# transponder-6_1_0.net
KiCad netlist of a schematic drawn in EAGLE
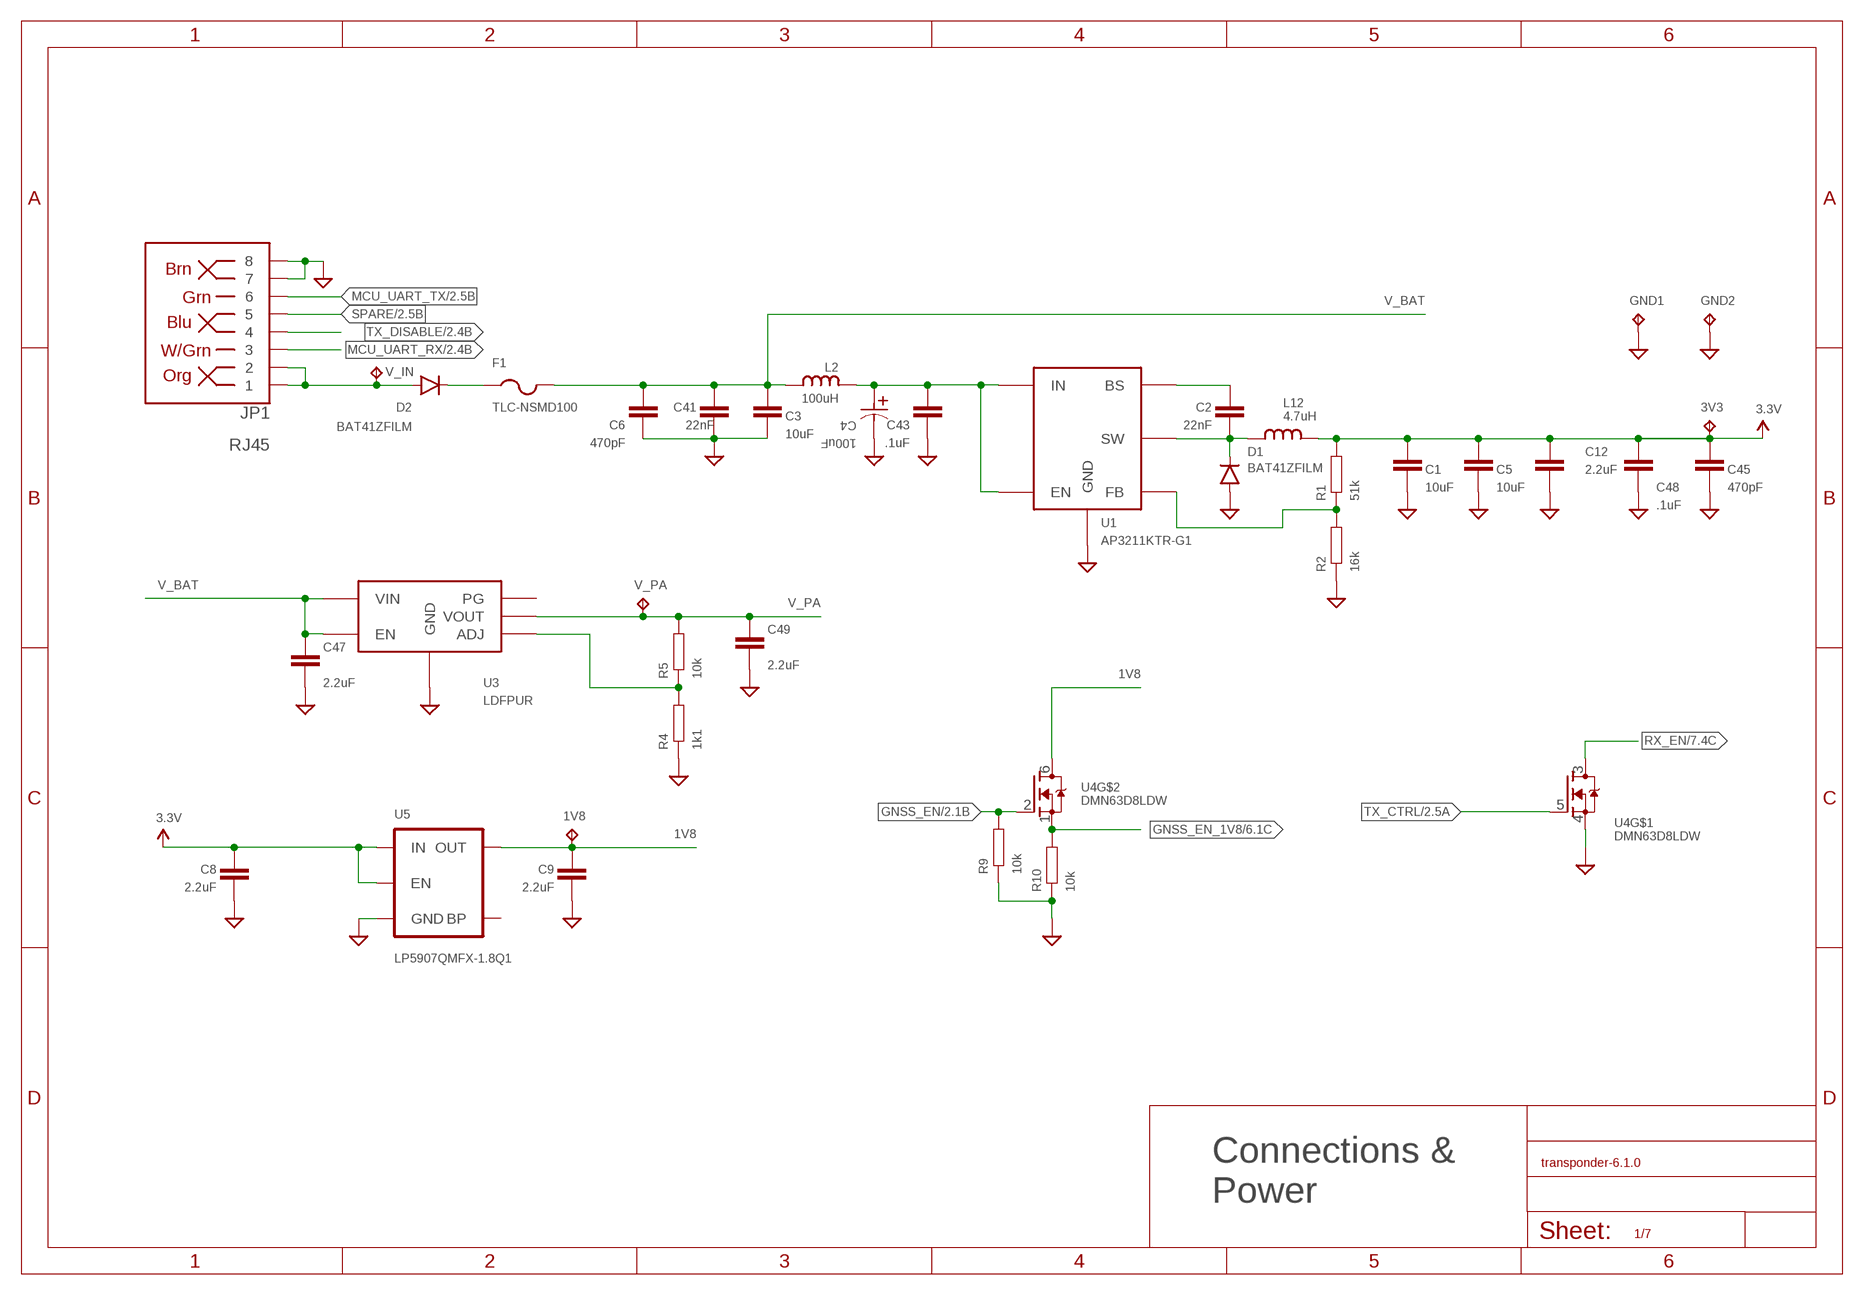
[diagram p0: schematic, sheet 1]
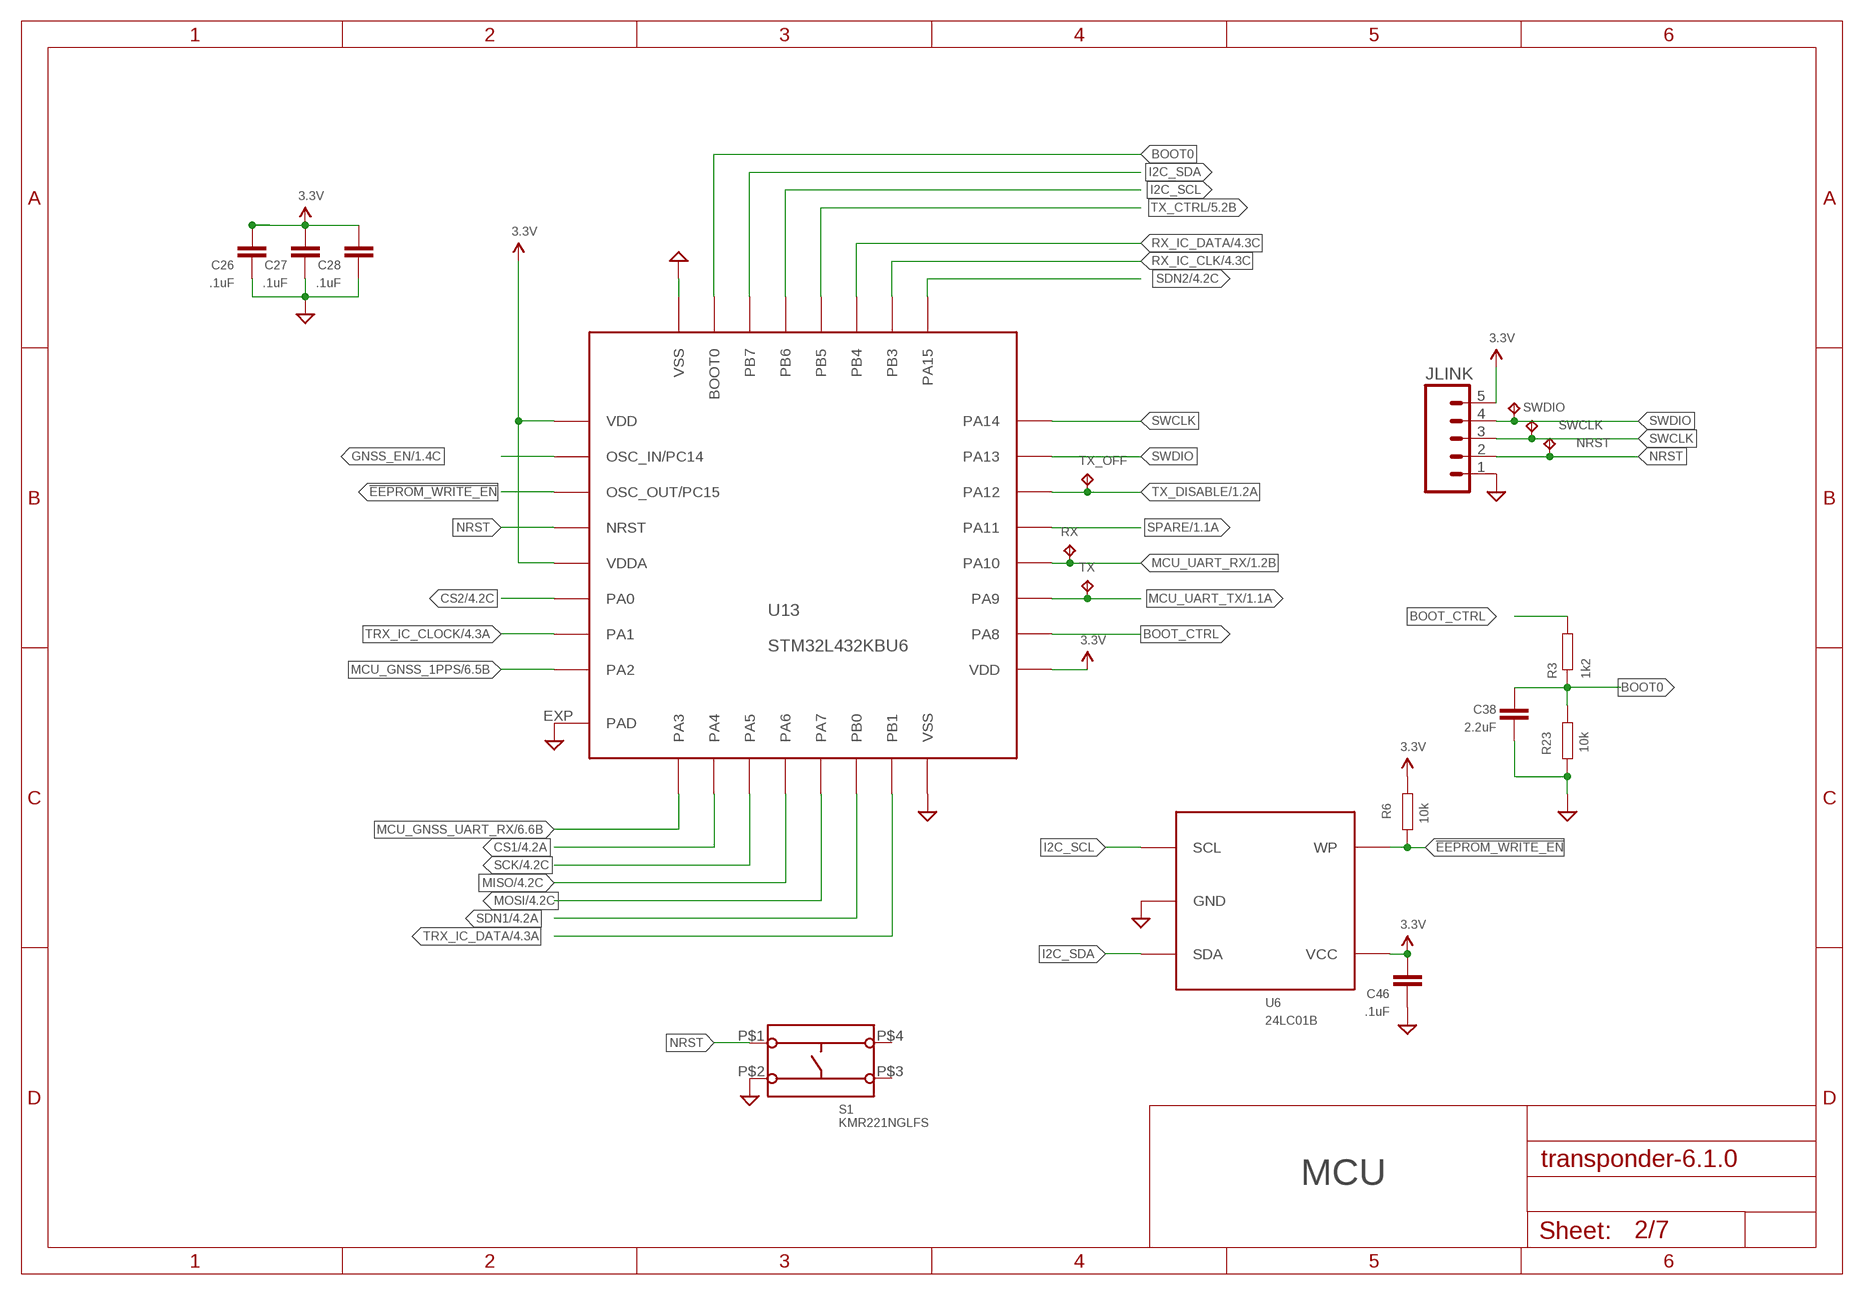
[diagram p1: schematic, sheet 2]
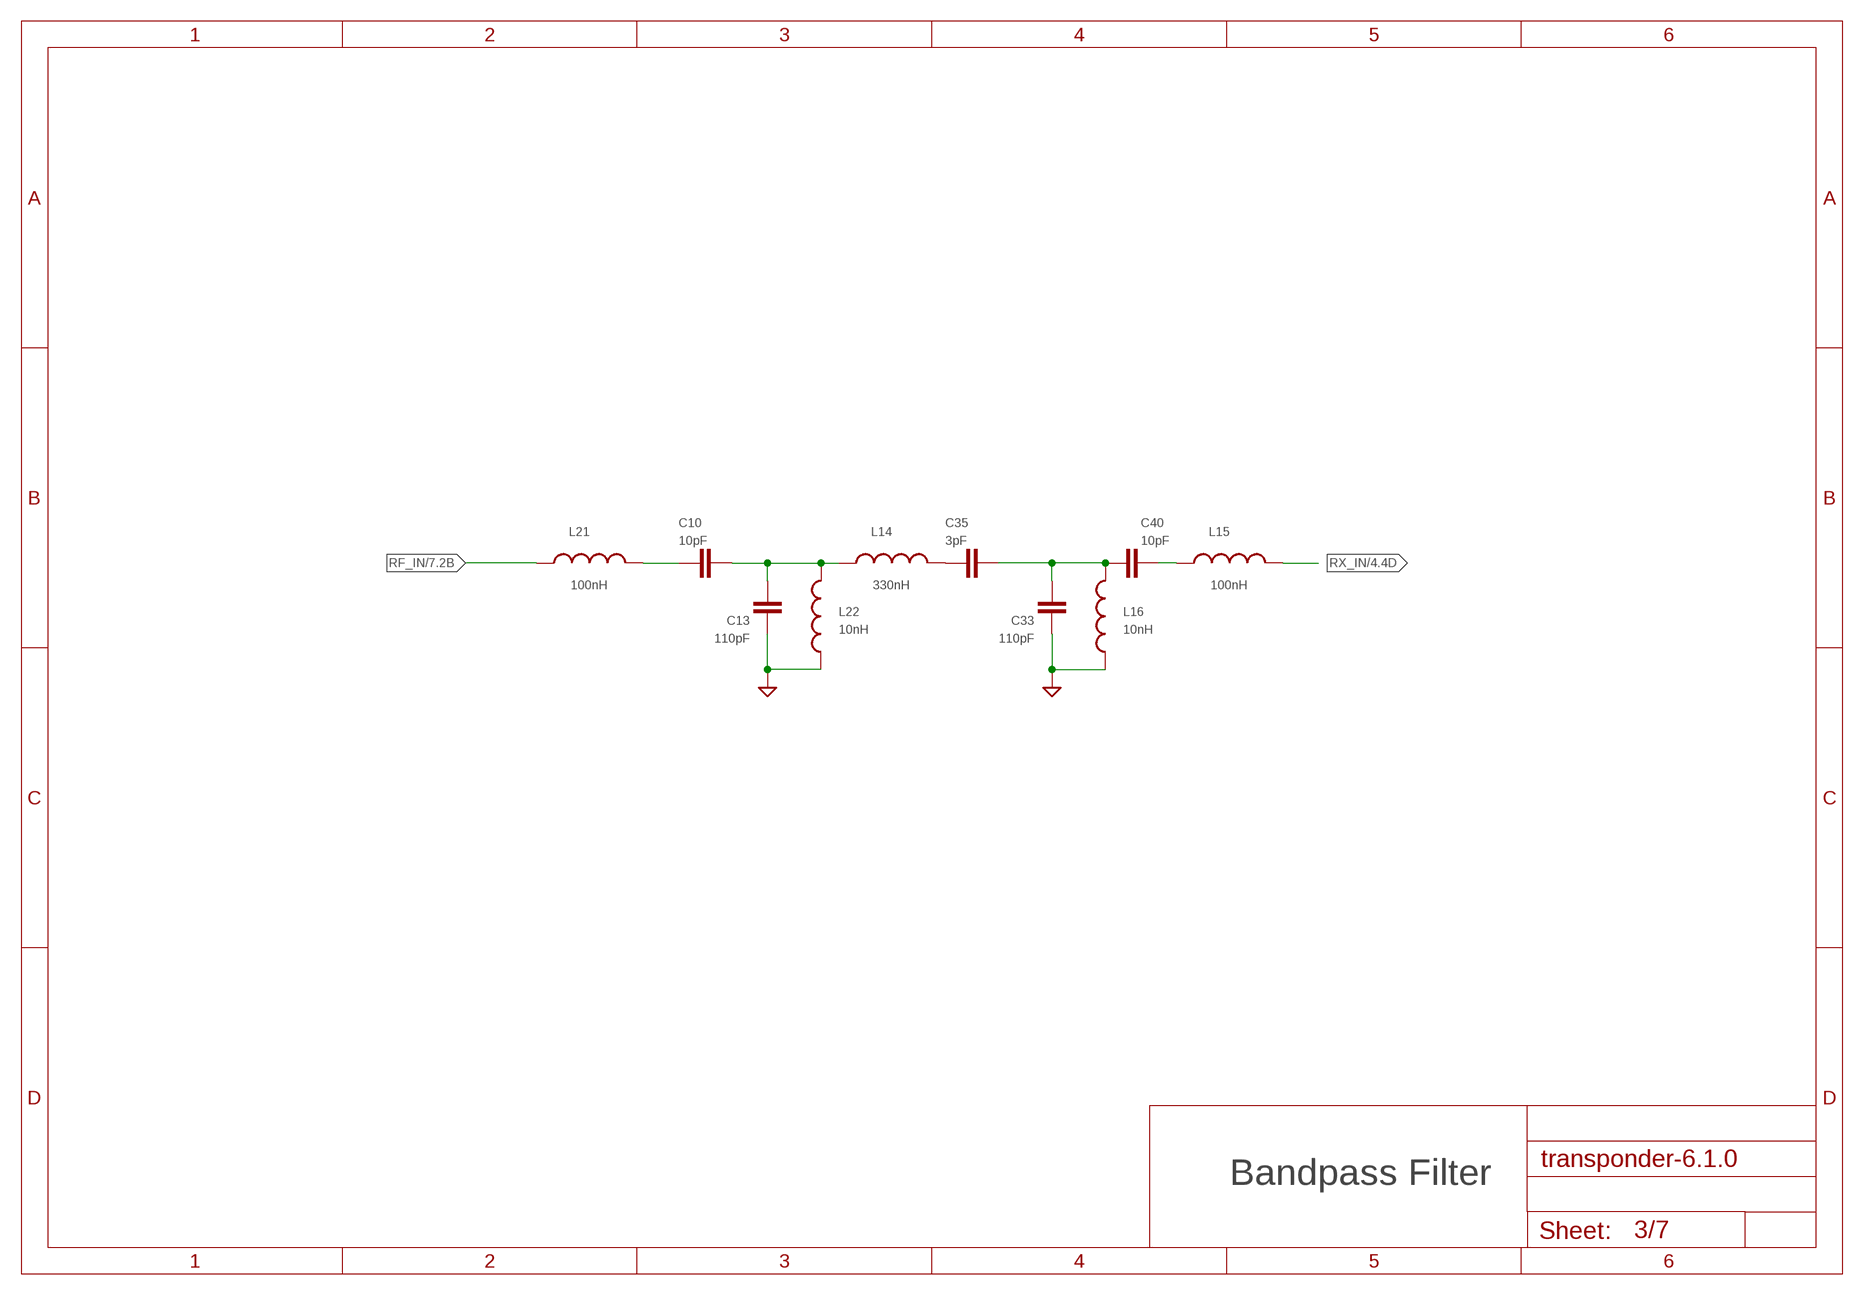
[diagram p2: schematic, sheet 3]
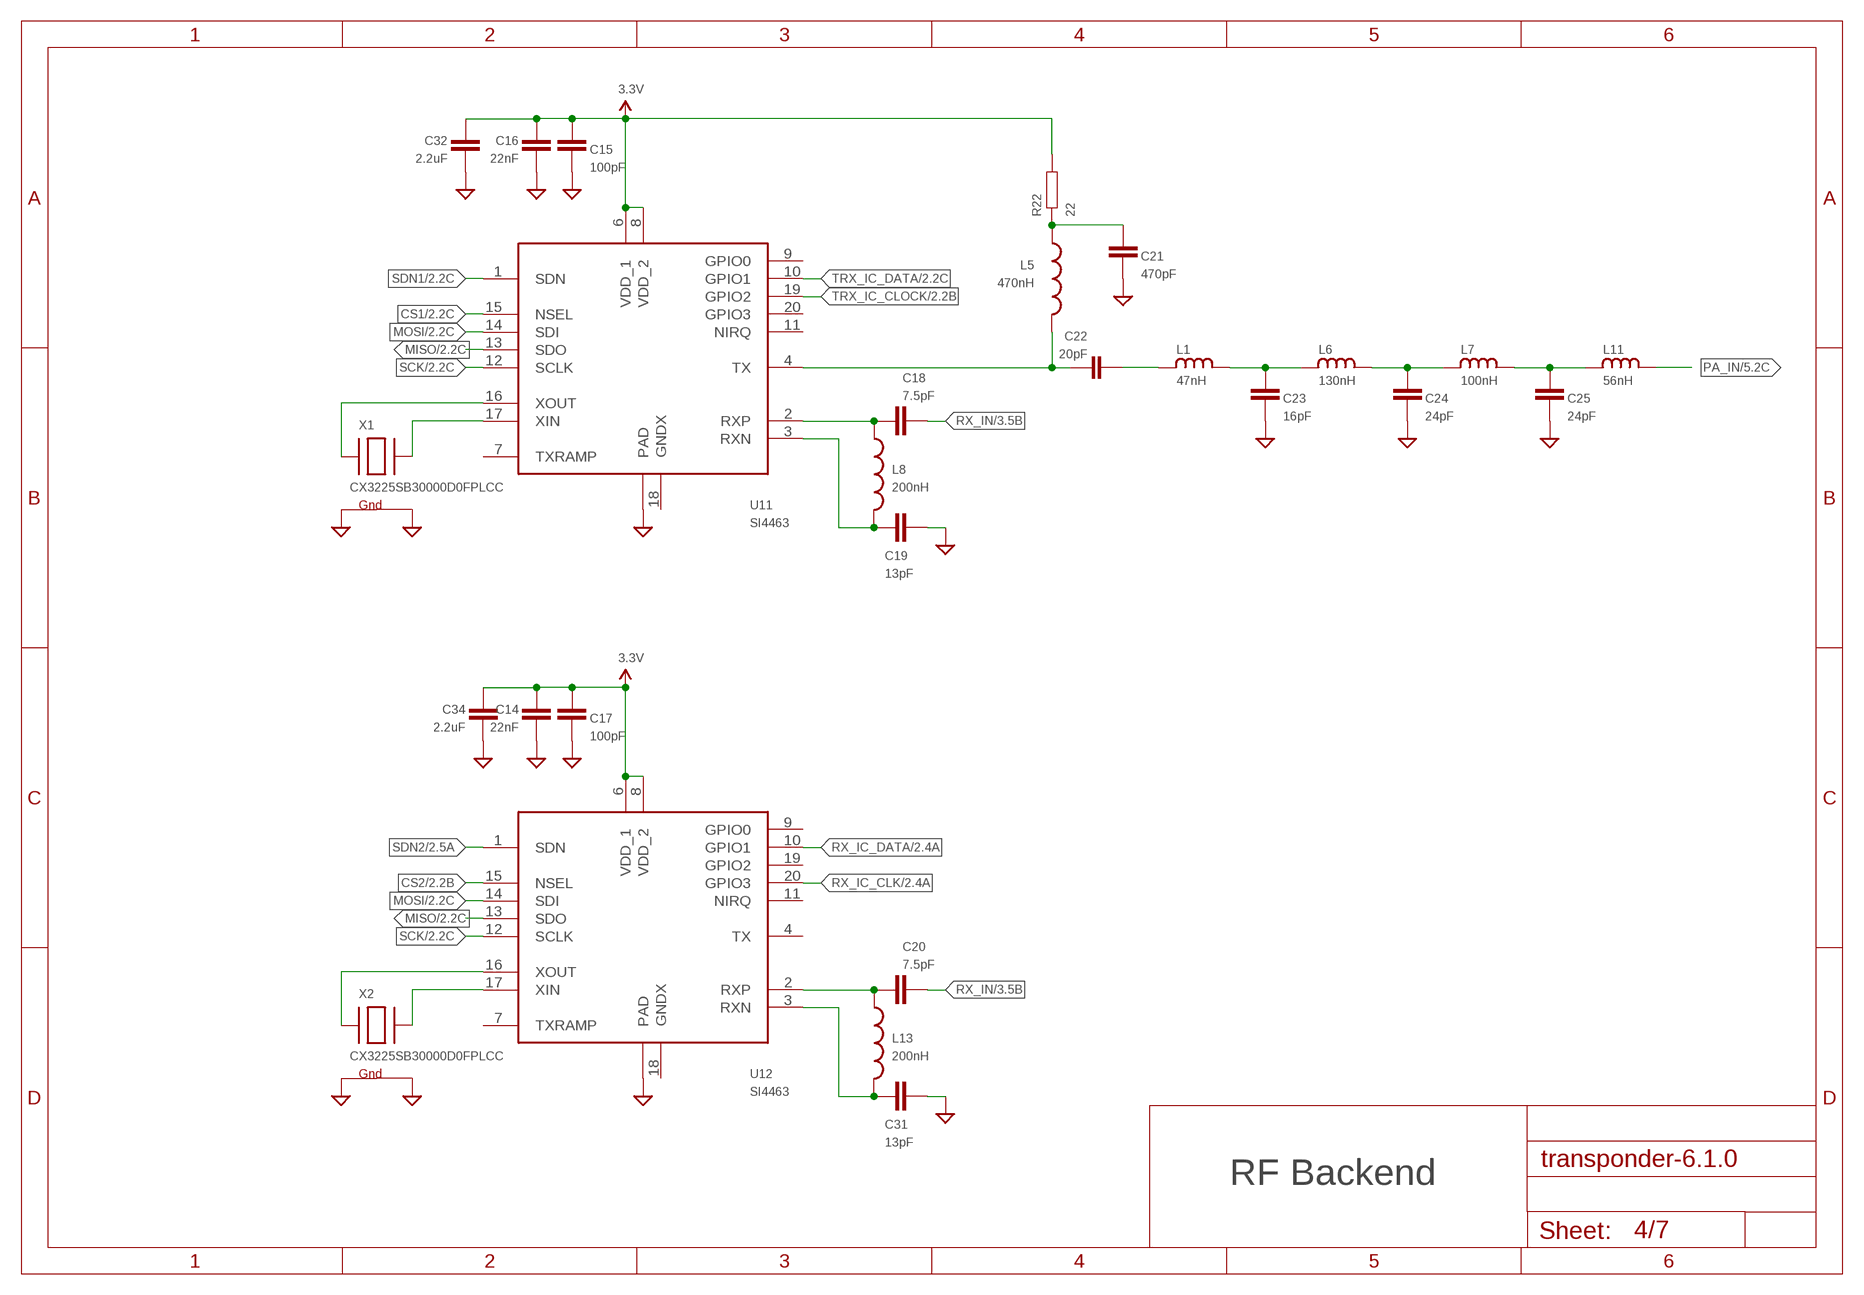
[diagram p3: schematic, sheet 4]
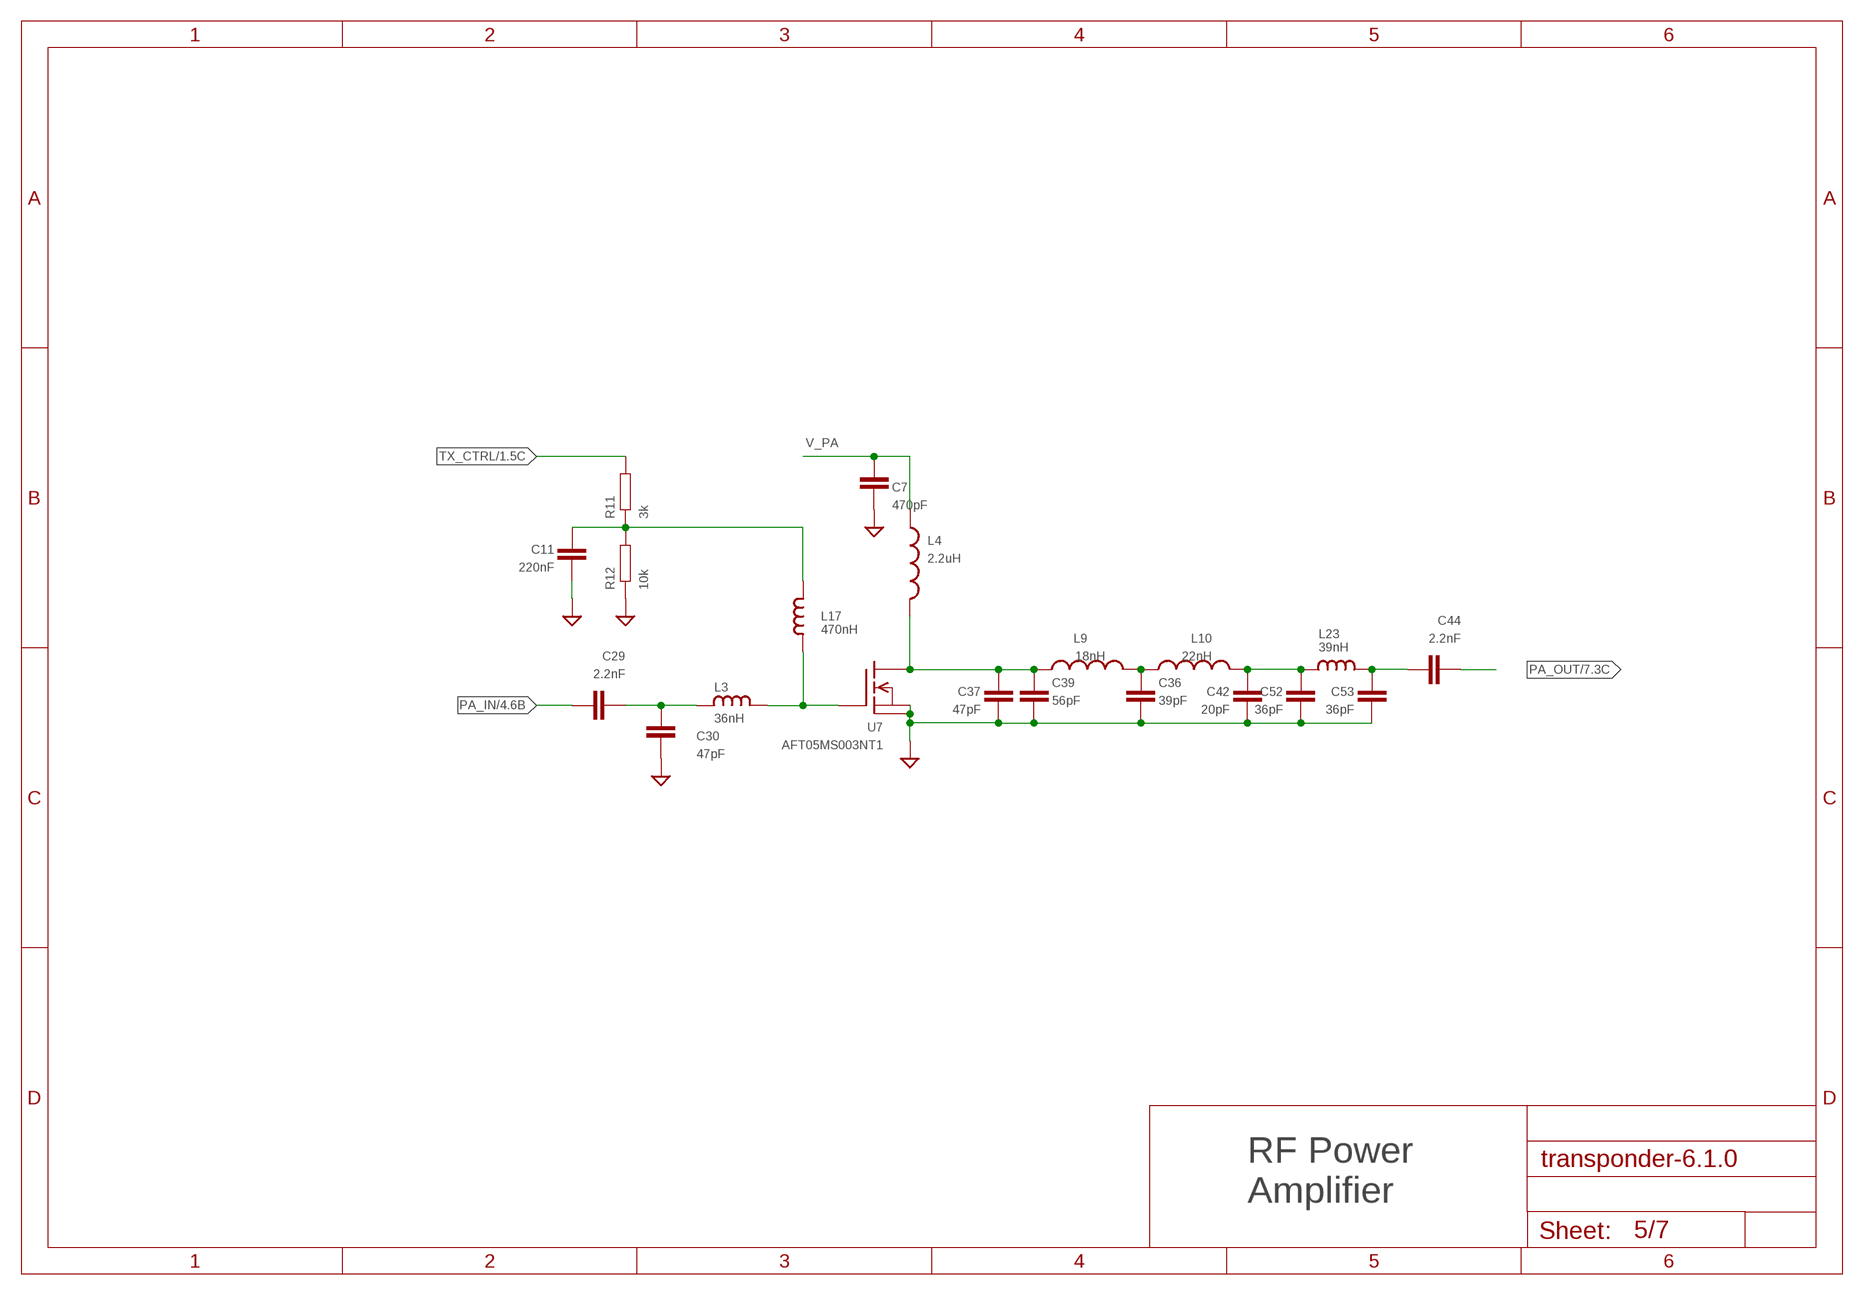
[diagram p4: schematic, sheet 5]
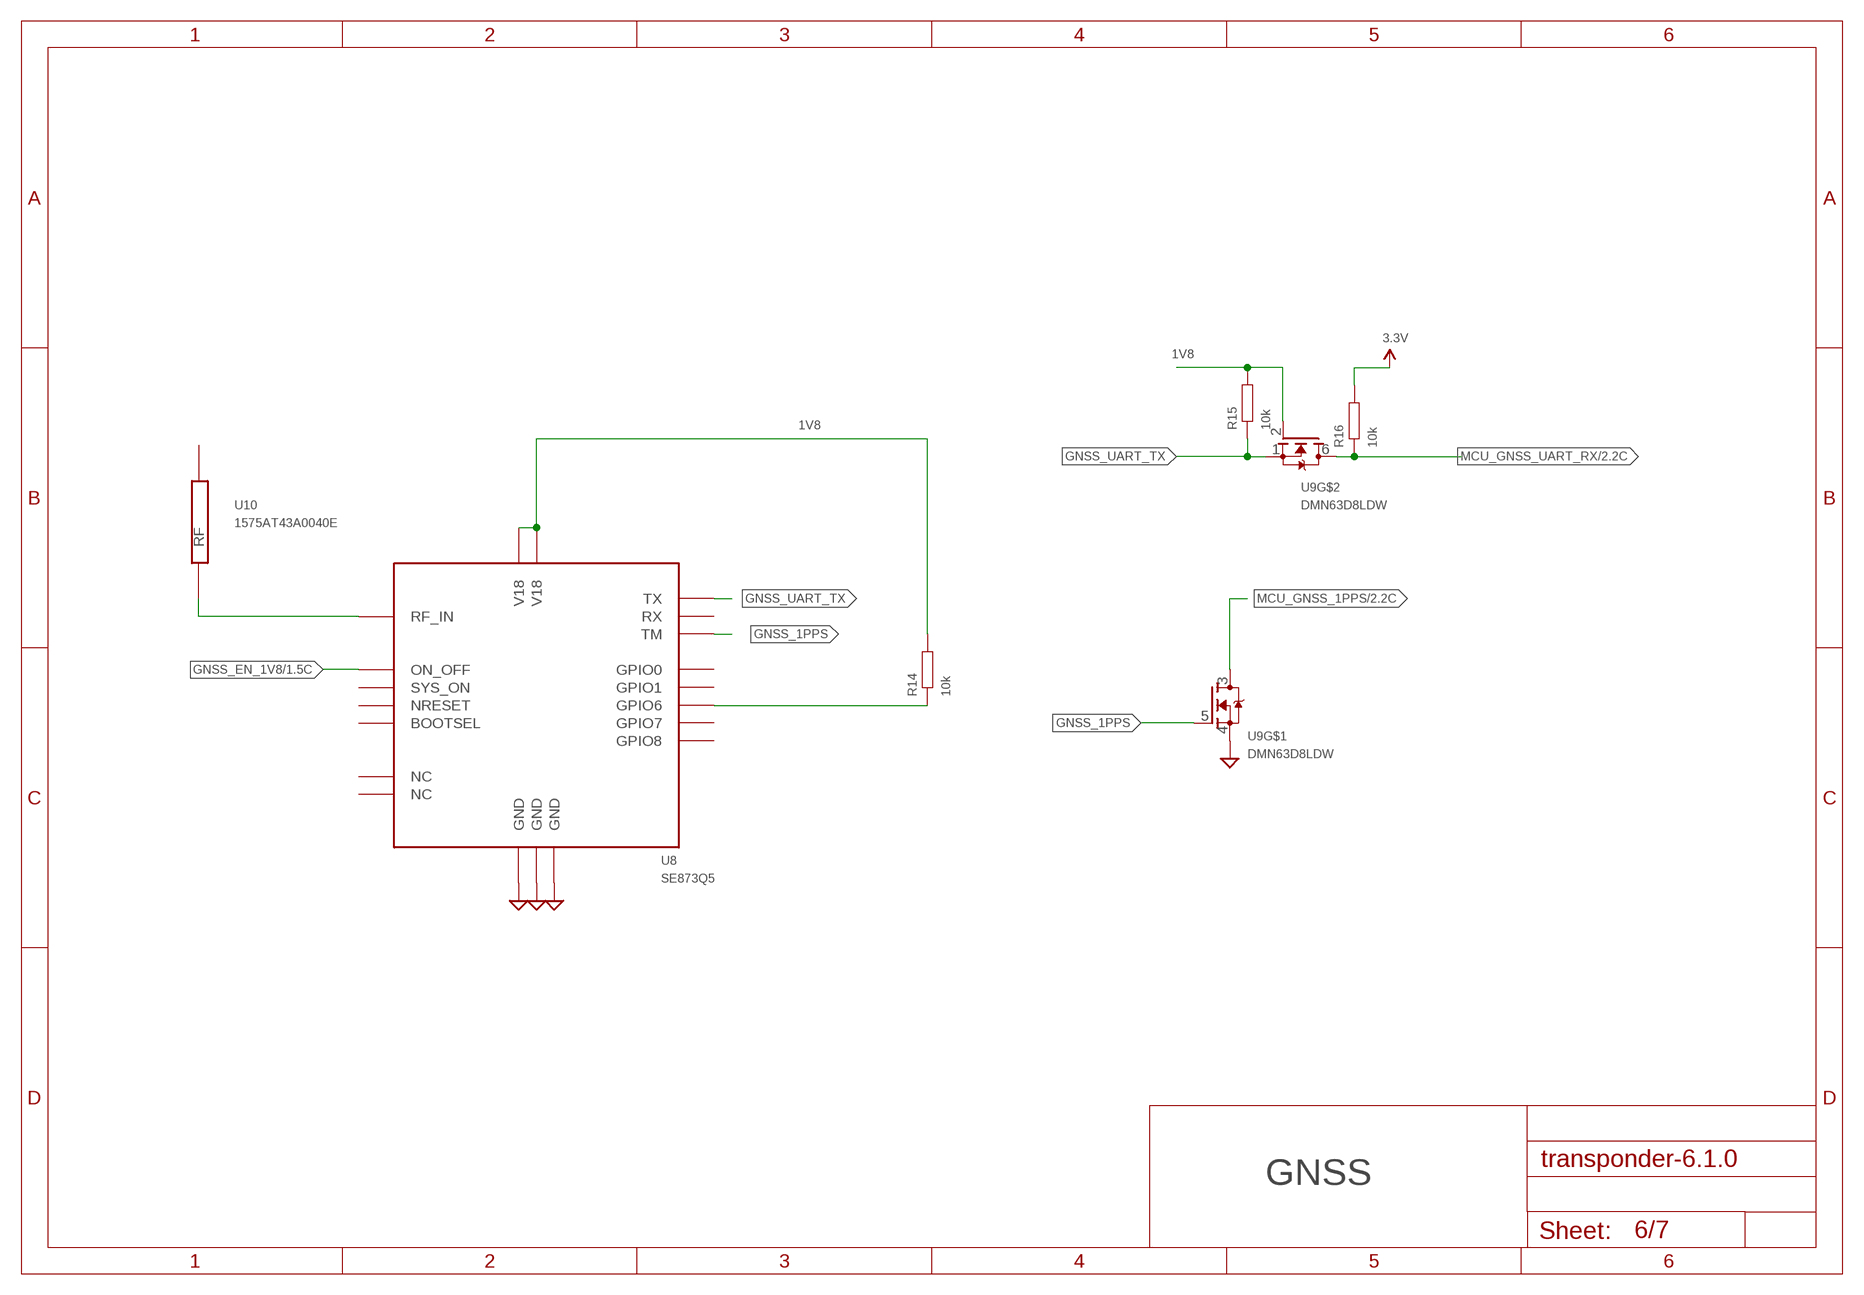
[diagram p5: schematic, sheet 6]
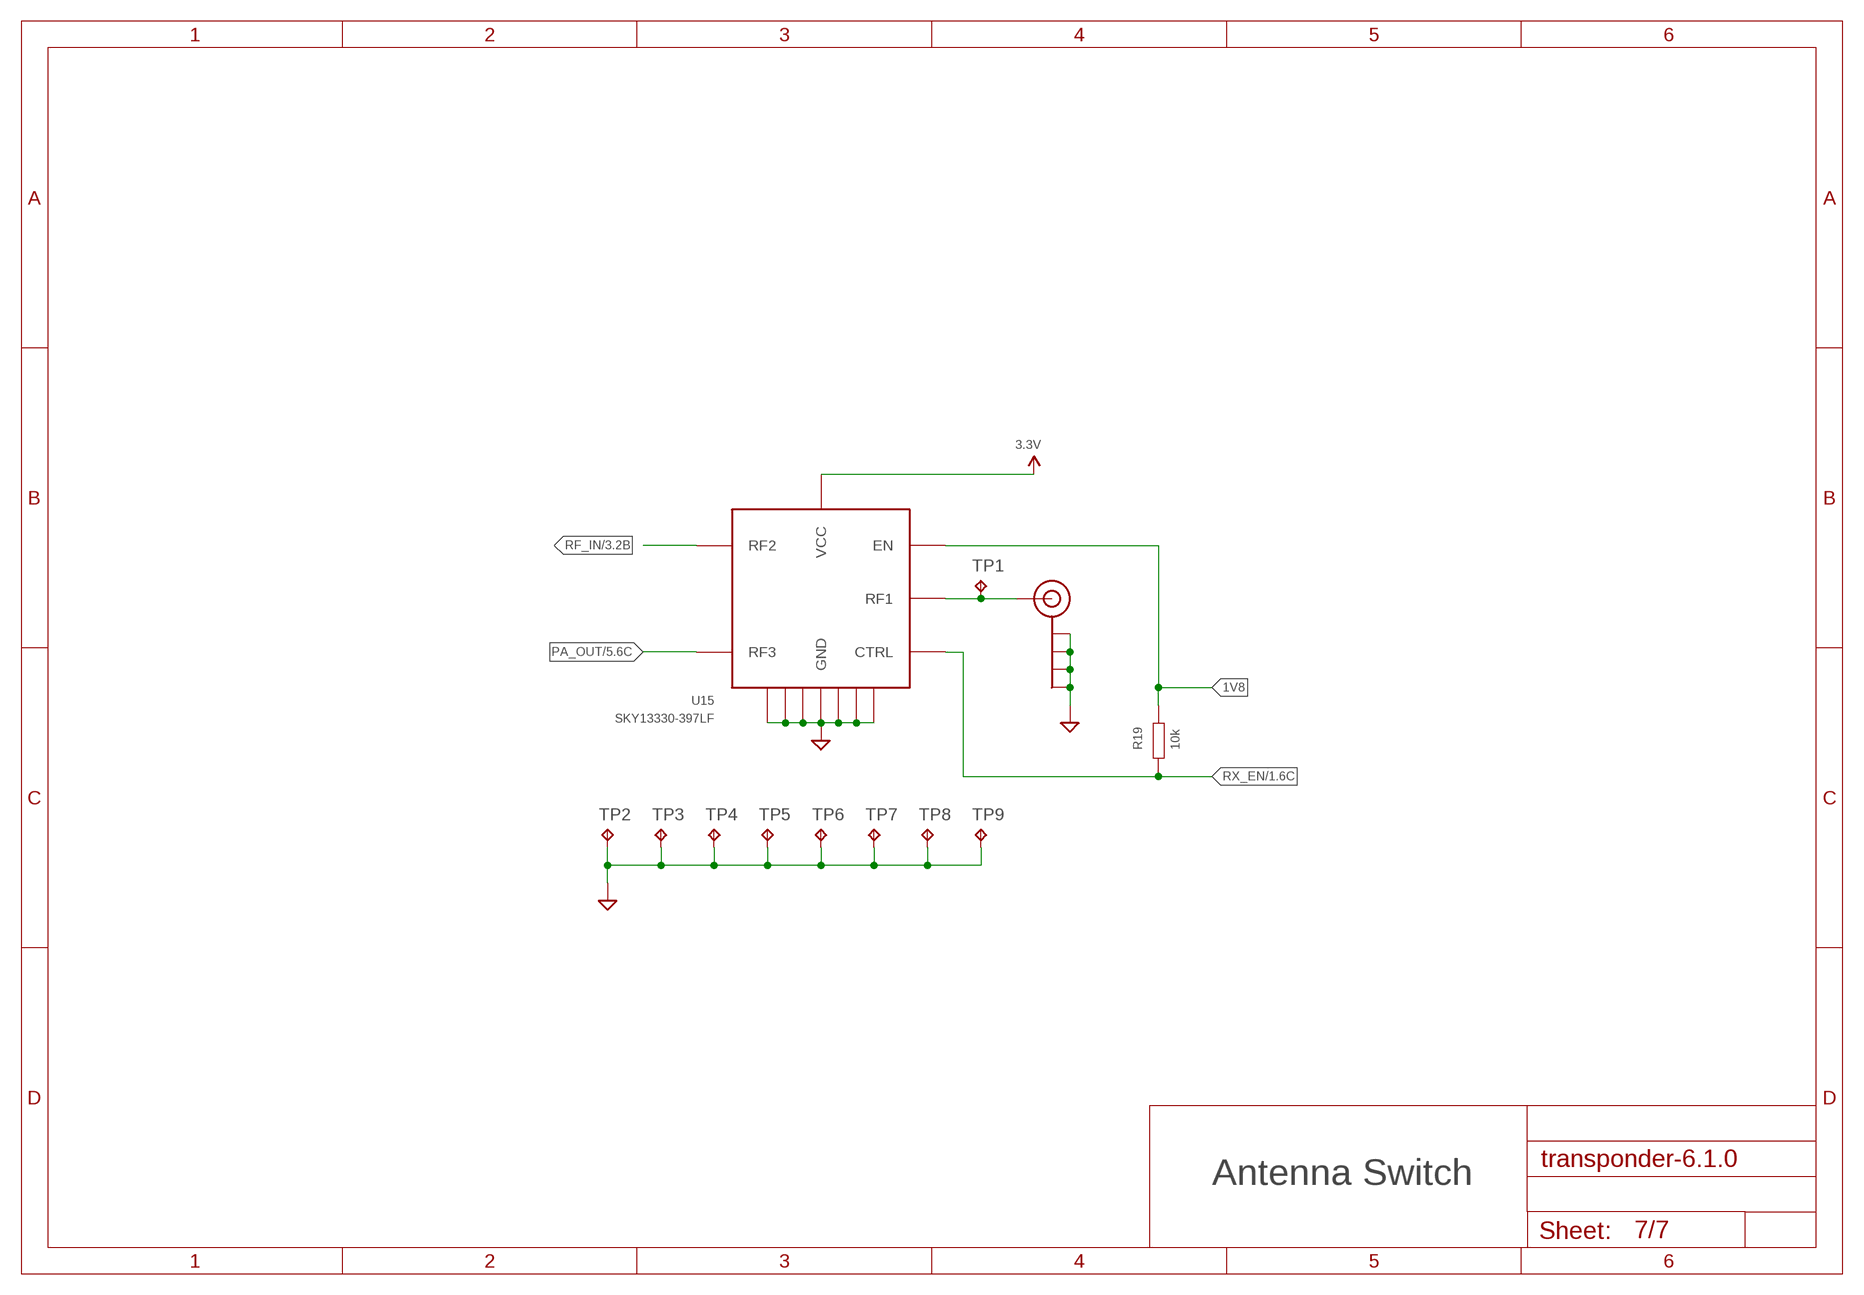
[diagram p6: schematic, sheet 7]

(export (version "E")
  (design (tool "Eeschema 10.0.6"))
  (components
    (comp (ref "C10")
      (value "10pF")
      (footprint "eagle-import:0603-CAP")
      (libsource (lib "eagle-import") (part "CAP0603-CAP"))
    )
    (comp (ref "C13")
      (value "110pF")
      (footprint "eagle-import:0603-CAP")
      (libsource (lib "eagle-import") (part "CAP0603-CAP"))
    )
    (comp (ref "C33")
      (value "110pF")
      (footprint "eagle-import:0603-CAP")
      (libsource (lib "eagle-import") (part "CAP0603-CAP"))
    )
    (comp (ref "C35")
      (value "3pF")
      (footprint "eagle-import:0603-CAP")
      (libsource (lib "eagle-import") (part "CAP0603-CAP"))
    )
    (comp (ref "C40")
      (value "10pF")
      (footprint "eagle-import:0603-CAP")
      (libsource (lib "eagle-import") (part "CAP0603-CAP"))
    )
    (comp (ref "L14")
      (value "330nH")
      (footprint "eagle-import:0603")
      (libsource (lib "eagle-import") (part "SparkFun-Passives_INDUCTOR0603"))
    )
    (comp (ref "L15")
      (value "100nH")
      (footprint "eagle-import:0603")
      (libsource (lib "eagle-import") (part "SparkFun-Passives_INDUCTOR0603"))
    )
    (comp (ref "L16")
      (value "10nH")
      (footprint "eagle-import:0603")
      (libsource (lib "eagle-import") (part "SparkFun-Passives_INDUCTOR0603"))
    )
    (comp (ref "L21")
      (value "100nH")
      (footprint "eagle-import:0603")
      (libsource (lib "eagle-import") (part "SparkFun-Passives_INDUCTOR0603"))
    )
    (comp (ref "L22")
      (value "10nH")
      (footprint "eagle-import:0603")
      (libsource (lib "eagle-import") (part "SparkFun-Passives_INDUCTOR0603"))
    )
    (comp (ref "C7")
      (value "470pF")
      (footprint "eagle-import:0603-CAP")
      (fields (field (name "PARTNO") "GCM1885C2A471JA16J"))
      (libsource (lib "eagle-import") (part "CAP0603-CAP"))
    )
    (comp (ref "C11")
      (value "220nF")
      (footprint "eagle-import:0603-CAP")
      (libsource (lib "eagle-import") (part "CAP0603-CAP"))
    )
    (comp (ref "C29")
      (value "2.2nF")
      (footprint "eagle-import:0603-CAP")
      (fields (field (name "PARTNO") "GRM1885C1H222JA01J"))
      (libsource (lib "eagle-import") (part "CAP0603-CAP"))
    )
    (comp (ref "C30")
      (value "47pF")
      (footprint "eagle-import:0603-CAP")
      (fields (field (name "PARTNO") "Murata Electronics"))
      (libsource (lib "eagle-import") (part "CAP0603-CAP"))
    )
    (comp (ref "C36")
      (value "39pF")
      (footprint "eagle-import:0603-CAP")
      (fields (field (name "PARTNO") "GRM1885C1H390JA01D"))
      (libsource (lib "eagle-import") (part "CAP0603-CAP"))
    )
    (comp (ref "C37")
      (value "47pF")
      (footprint "eagle-import:0603-CAP")
      (fields (field (name "PARTNO") "Murata Electronics"))
      (libsource (lib "eagle-import") (part "CAP0603-CAP"))
    )
    (comp (ref "C39")
      (value "56pF")
      (footprint "eagle-import:0603-CAP")
      (fields (field (name "PARTNO") "GRM1885C1H560JA01D"))
      (libsource (lib "eagle-import") (part "CAP0603-CAP"))
    )
    (comp (ref "C42")
      (value "20pF")
      (footprint "eagle-import:0603-CAP")
      (fields (field (name "PARTNO") "GRM1885C1H200JA01D"))
      (libsource (lib "eagle-import") (part "CAP0603-CAP"))
    )
    (comp (ref "C44")
      (value "2.2nF")
      (footprint "eagle-import:0603-CAP")
      (fields (field (name "PARTNO") "GRM1885C1H222JA01J"))
      (libsource (lib "eagle-import") (part "CAP0603-CAP"))
    )
    (comp (ref "C52")
      (value "36pF")
      (footprint "eagle-import:0603-CAP")
      (libsource (lib "eagle-import") (part "CAP0603-CAP"))
    )
    (comp (ref "C53")
      (value "36pF")
      (footprint "eagle-import:0603-CAP")
      (libsource (lib "eagle-import") (part "CAP0603-CAP"))
    )
    (comp (ref "L3")
      (value "36nH")
      (footprint "eagle-import:0603")
      (libsource (lib "eagle-import") (part "INDUCTOR0603"))
    )
    (comp (ref "L4")
      (value "2.2uH")
      (footprint "eagle-import:0805")
      (fields (field (name "PARTNO") "BRC2012T2R2MD"))
      (libsource (lib "eagle-import") (part "SparkFun-Passives_INDUCTOR0805"))
    )
    (comp (ref "L9")
      (value "18nH")
      (footprint "eagle-import:0603")
      (fields (field (name "PARTNO") "LQW18AN18NG00D"))
      (libsource (lib "eagle-import") (part "SparkFun-Passives_INDUCTOR0603"))
    )
    (comp (ref "L10")
      (value "22nH")
      (footprint "eagle-import:0603")
      (fields (field (name "PARTNO") "LQW18AN22NJ00D"))
      (libsource (lib "eagle-import") (part "SparkFun-Passives_INDUCTOR0603"))
    )
    (comp (ref "L17")
      (value "470nH")
      (footprint "eagle-import:0603")
      (fields (field (name "PARTNO") "HK1608R47J-T"))
      (libsource (lib "eagle-import") (part "INDUCTOR0603"))
    )
    (comp (ref "L23")
      (value "39nH")
      (footprint "eagle-import:0603")
      (libsource (lib "eagle-import") (part "INDUCTOR0603"))
    )
    (comp (ref "R11")
      (value "3k")
      (footprint "eagle-import:0603-RES")
      (fields (field (name "PARTNO") "RC0603JR-073KL"))
      (libsource (lib "eagle-import") (part "RESISTOR0603-RES"))
    )
    (comp (ref "R12")
      (value "10k")
      (footprint "eagle-import:0603-RES")
      (fields (field (name "PARTNO") "RC0603JR-0710KL"))
      (libsource (lib "eagle-import") (part "RESISTOR0603-RES"))
    )
    (comp (ref "U7")
      (value "AFT05MS003NT1")
      (footprint "eagle-import:SOT-89")
      (libsource (lib "eagle-import") (part "AFT0SMS003N"))
    )
    (comp (ref "C26")
      (value ".1uF")
      (footprint "eagle-import:0603-CAP")
      (fields (field (name "PARTNO") "EMK107B7104KAHT"))
      (libsource (lib "eagle-import") (part "CAP0603-CAP"))
    )
    (comp (ref "C27")
      (value ".1uF")
      (footprint "eagle-import:0603-CAP")
      (fields (field (name "PARTNO") "EMK107B7104KAHT"))
      (libsource (lib "eagle-import") (part "CAP0603-CAP"))
    )
    (comp (ref "C28")
      (value ".1uF")
      (footprint "eagle-import:0603-CAP")
      (fields (field (name "PARTNO") "EMK107B7104KAHT"))
      (libsource (lib "eagle-import") (part "CAP0603-CAP"))
    )
    (comp (ref "C38")
      (value "2.2uF")
      (footprint "eagle-import:0603-CAP")
      (fields (field (name "PARTNO") "EMK107BJ225KA-T"))
      (libsource (lib "eagle-import") (part "CAP0603-CAP"))
    )
    (comp (ref "C46")
      (value ".1uF")
      (footprint "eagle-import:0603-CAP")
      (fields (field (name "PARTNO") "EMK107B7104KAHT"))
      (libsource (lib "eagle-import") (part "CAP0603-CAP"))
    )
    (comp (ref "JLINK")
      (value "M05PTH")
      (footprint "eagle-import:1X05")
      (libsource (lib "eagle-import") (part "M05PTH"))
    )
    (comp (ref "NRST")
      (value "TPTP12R")
      (footprint "eagle-import:TP12R")
      (libsource (lib "eagle-import") (part "TPTP12R"))
    )
    (comp (ref "R3")
      (value "1k2")
      (footprint "eagle-import:0603-RES")
      (fields (field (name "PARTNO") "RC0603JR-071K2L"))
      (libsource (lib "eagle-import") (part "RESISTOR0603-RES"))
    )
    (comp (ref "R6")
      (value "10k")
      (footprint "eagle-import:0603-RES")
      (fields (field (name "PARTNO") "RC0603JR-0710KL"))
      (libsource (lib "eagle-import") (part "RESISTOR0603-RES"))
    )
    (comp (ref "R23")
      (value "10k")
      (footprint "eagle-import:0603-RES")
      (fields (field (name "PARTNO") "RC0603JR-0710KL"))
      (libsource (lib "eagle-import") (part "RESISTOR0603-RES"))
    )
    (comp (ref "RX")
      (value "TPTP12R")
      (footprint "eagle-import:TP12R")
      (libsource (lib "eagle-import") (part "TPTP12R"))
    )
    (comp (ref "S1")
      (value "KMR221NGLFS")
      (footprint "eagle-import:KMR221NGLFS")
      (libsource (lib "eagle-import") (part "KMR221NGLFS"))
    )
    (comp (ref "SWCLK")
      (value "TPTP12R")
      (footprint "eagle-import:TP12R")
      (libsource (lib "eagle-import") (part "TPTP12R"))
    )
    (comp (ref "SWDIO")
      (value "TPTP12R")
      (footprint "eagle-import:TP12R")
      (libsource (lib "eagle-import") (part "TPTP12R"))
    )
    (comp (ref "TX")
      (value "TPTP12R")
      (footprint "eagle-import:TP12R")
      (libsource (lib "eagle-import") (part "TPTP12R"))
    )
    (comp (ref "TX_OFF")
      (value "TPTP12R")
      (footprint "eagle-import:TP12R")
      (libsource (lib "eagle-import") (part "TPTP12R"))
    )
    (comp (ref "U6")
      (value "24LC01B")
      (footprint "eagle-import:SOT23-5")
      (fields (field (name "PARTNO") "24LC01BT-I/OT"))
      (libsource (lib "eagle-import") (part "24LC01B"))
    )
    (comp (ref "U13")
      (value "STM32L432KBU6")
      (footprint "eagle-import:QFN32")
      (fields (field (name "PARTNO") "STM32L431KBU6"))
      (libsource (lib "eagle-import") (part "STM32L432KXXX"))
    )
    (comp (ref "1V8")
      (value "TPTP12R")
      (footprint "eagle-import:TP12R")
      (libsource (lib "eagle-import") (part "TPTP12R"))
    )
    (comp (ref "3V3")
      (value "TPTP16R")
      (footprint "eagle-import:TP16R")
      (libsource (lib "eagle-import") (part "TPTP16R"))
    )
    (comp (ref "C1")
      (value "10uF")
      (footprint "eagle-import:0805")
      (fields (field (name "PARTNO") " EMK212ABJ106KG-T"))
      (libsource (lib "eagle-import") (part "CAP0805"))
    )
    (comp (ref "C2")
      (value "22nF")
      (footprint "eagle-import:0603-CAP")
      (fields (field (name "PARTNO") "GRM188R71E223KA01D"))
      (libsource (lib "eagle-import") (part "CAP0603-CAP"))
    )
    (comp (ref "C3")
      (value "10uF")
      (footprint "eagle-import:0805")
      (fields (field (name "PARTNO") " EMK212ABJ106KG-T"))
      (libsource (lib "eagle-import") (part "CAP0805"))
    )
    (comp (ref "C4")
      (value "100uF")
      (footprint "eagle-import:PCAP_6.3X5.4-ELECT")
      (fields (field (name "MF") "Nichicon") (field (name "MP") "UWX1C101MCL1GB"))
      (libsource (lib "eagle-import") (part "UWX1C101MCL1GB"))
    )
    (comp (ref "C5")
      (value "10uF")
      (footprint "eagle-import:0805")
      (fields (field (name "PARTNO") " EMK212ABJ106KG-T"))
      (libsource (lib "eagle-import") (part "CAP0805"))
    )
    (comp (ref "C6")
      (value "470pF")
      (footprint "eagle-import:0603-CAP")
      (fields (field (name "PARTNO") "GCM1885C2A471JA16J"))
      (libsource (lib "eagle-import") (part "CAP0603-CAP"))
    )
    (comp (ref "C8")
      (value "2.2uF")
      (footprint "eagle-import:0603-CAP")
      (fields (field (name "PARTNO") "EMK107BJ225KA-T"))
      (libsource (lib "eagle-import") (part "CAP0603-CAP"))
    )
    (comp (ref "C9")
      (value "2.2uF")
      (footprint "eagle-import:0603-CAP")
      (fields (field (name "PARTNO") "EMK107BJ225KA-T"))
      (libsource (lib "eagle-import") (part "CAP0603-CAP"))
    )
    (comp (ref "C12")
      (value "2.2uF")
      (footprint "eagle-import:0603-CAP")
      (fields (field (name "PARTNO") "EMK107BJ225KA-T"))
      (libsource (lib "eagle-import") (part "CAP0603-CAP"))
    )
    (comp (ref "C41")
      (value "22nF")
      (footprint "eagle-import:0603-CAP")
      (fields (field (name "PARTNO") "GRM188R71E223KA01D"))
      (libsource (lib "eagle-import") (part "CAP0603-CAP"))
    )
    (comp (ref "C43")
      (value ".1uF")
      (footprint "eagle-import:0603-CAP")
      (fields (field (name "PARTNO") "EMK107B7104KAHT"))
      (libsource (lib "eagle-import") (part "CAP0603-CAP"))
    )
    (comp (ref "C45")
      (value "470pF")
      (footprint "eagle-import:0603-CAP")
      (fields (field (name "PARTNO") "GCM1885C2A471JA16J"))
      (libsource (lib "eagle-import") (part "CAP0603-CAP"))
    )
    (comp (ref "C47")
      (value "2.2uF")
      (footprint "eagle-import:0603-CAP")
      (fields (field (name "PARTNO") "EMK107BJ225KA-T"))
      (libsource (lib "eagle-import") (part "CAP0603-CAP"))
    )
    (comp (ref "C48")
      (value ".1uF")
      (footprint "eagle-import:0603-CAP")
      (fields (field (name "PARTNO") "EMK107B7104KAHT"))
      (libsource (lib "eagle-import") (part "CAP0603-CAP"))
    )
    (comp (ref "C49")
      (value "2.2uF")
      (footprint "eagle-import:0603-CAP")
      (fields (field (name "PARTNO") "EMK107BJ225KA-T"))
      (libsource (lib "eagle-import") (part "CAP0603-CAP"))
    )
    (comp (ref "D1")
      (value "BAT41ZFILM")
      (footprint "eagle-import:SOD-123")
      (libsource (lib "eagle-import") (part "DIODESOD123"))
    )
    (comp (ref "D2")
      (value "BAT41ZFILM")
      (footprint "eagle-import:SOD-123")
      (libsource (lib "eagle-import") (part "DIODESOD123"))
    )
    (comp (ref "F1")
      (value "TLC-NSMD100")
      (footprint "eagle-import:R1206")
      (libsource (lib "eagle-import") (part "PTCFUSE-1206"))
    )
    (comp (ref "GND1")
      (value "TPTP16R")
      (footprint "eagle-import:TP16R")
      (libsource (lib "eagle-import") (part "TPTP16R"))
    )
    (comp (ref "GND2")
      (value "TPTP16R")
      (footprint "eagle-import:TP16R")
      (libsource (lib "eagle-import") (part "TPTP16R"))
    )
    (comp (ref "JP1")
      (value "RJ45")
      (footprint "eagle-import:RJ45-8")
      (libsource (lib "eagle-import") (part "RJ45-8PTH"))
    )
    (comp (ref "L2")
      (value "100uH")
      (footprint "eagle-import:1206")
      (fields (field (name "PARTNO") "CBC3225T101KRV"))
      (libsource (lib "eagle-import") (part "INDUCTOR1206"))
    )
    (comp (ref "L12")
      (value "4.7uH")
      (footprint "eagle-import:0805")
      (fields (field (name "PARTNO") "MLZ2012M4R7WT000"))
      (libsource (lib "eagle-import") (part "INDUCTOR0805"))
    )
    (comp (ref "R1")
      (value "51k")
      (footprint "eagle-import:0603-RES")
      (fields (field (name "PARTNO") "RC0603JR-0751KL"))
      (libsource (lib "eagle-import") (part "RESISTOR0603-RES"))
    )
    (comp (ref "R2")
      (value "16k")
      (footprint "eagle-import:0603-RES")
      (fields (field (name "PARTNO") "RC0603FR-1016KL"))
      (libsource (lib "eagle-import") (part "RESISTOR0603-RES"))
    )
    (comp (ref "R4")
      (value "1k1")
      (footprint "eagle-import:0603-RES")
      (fields (field (name "PARTNO") "RC0603JR-071K1L"))
      (libsource (lib "eagle-import") (part "RESISTOR0603-RES"))
    )
    (comp (ref "R5")
      (value "10k")
      (footprint "eagle-import:0603-RES")
      (fields (field (name "PARTNO") "RC0603JR-0710KL"))
      (libsource (lib "eagle-import") (part "RESISTOR0603-RES"))
    )
    (comp (ref "R9")
      (value "10k")
      (footprint "eagle-import:0603-RES")
      (fields (field (name "PARTNO") "RC0603JR-0710KL"))
      (libsource (lib "eagle-import") (part "RESISTOR0603-RES"))
    )
    (comp (ref "R10")
      (value "10k")
      (footprint "eagle-import:0603-RES")
      (fields (field (name "PARTNO") "RC0603JR-0710KL"))
      (libsource (lib "eagle-import") (part "RESISTOR0603-RES"))
    )
    (comp (ref "U1")
      (value "AP3211KTR-G1")
      (footprint "eagle-import:SOT23-6")
      (libsource (lib "eagle-import") (part "AP3211"))
    )
    (comp (ref "U3")
      (value "LDFPUR")
      (footprint "eagle-import:DFN-6")
      (libsource (lib "eagle-import") (part "LDF"))
    )
    (comp (ref "U4")
      (value "DMN63D8LDW")
      (footprint "eagle-import:SOT363")
      (libsource (lib "eagle-import") (part "DMN63D8LDW"))
    )
    (comp (ref "U5")
      (value "LP5907QMFX-1.8Q1")
      (footprint "eagle-import:SOT23-5")
      (fields (field (name "PARTNO") "LP5907QMFX-1.8Q1 "))
      (libsource (lib "eagle-import") (part "V_REG_LDOSMD"))
    )
    (comp (ref "V_IN")
      (value "TPTP12R")
      (footprint "eagle-import:TP12R")
      (libsource (lib "eagle-import") (part "TPTP12R"))
    )
    (comp (ref "V_PA")
      (value "TPTP12R")
      (footprint "eagle-import:TP12R")
      (libsource (lib "eagle-import") (part "TPTP12R"))
    )
    (comp (ref "J$1")
      (value "SMA_EDGE")
      (footprint "eagle-import:SMA-EDGE")
      (libsource (lib "eagle-import") (part "SMA_EDGE"))
    )
    (comp (ref "R19")
      (value "10k")
      (footprint "eagle-import:0603-RES")
      (libsource (lib "eagle-import") (part "RESISTOR0603-RES"))
    )
    (comp (ref "TP1")
      (value "TPTP10R")
      (footprint "eagle-import:TP10R")
      (libsource (lib "eagle-import") (part "TPTP10R"))
    )
    (comp (ref "TP2")
      (value "TPTP08R")
      (footprint "eagle-import:TP08R")
      (libsource (lib "eagle-import") (part "TPTP08R"))
    )
    (comp (ref "TP3")
      (value "TPTP08R")
      (footprint "eagle-import:TP08R")
      (libsource (lib "eagle-import") (part "TPTP08R"))
    )
    (comp (ref "TP4")
      (value "TPTP08R")
      (footprint "eagle-import:TP08R")
      (libsource (lib "eagle-import") (part "TPTP08R"))
    )
    (comp (ref "TP5")
      (value "TPTP08R")
      (footprint "eagle-import:TP08R")
      (libsource (lib "eagle-import") (part "TPTP08R"))
    )
    (comp (ref "TP6")
      (value "TPTP08R")
      (footprint "eagle-import:TP08R")
      (libsource (lib "eagle-import") (part "TPTP08R"))
    )
    (comp (ref "TP7")
      (value "TPTP08R")
      (footprint "eagle-import:TP08R")
      (libsource (lib "eagle-import") (part "TPTP08R"))
    )
    (comp (ref "TP8")
      (value "TPTP08R")
      (footprint "eagle-import:TP08R")
      (libsource (lib "eagle-import") (part "TPTP08R"))
    )
    (comp (ref "TP9")
      (value "TPTP08R")
      (footprint "eagle-import:TP08R")
      (libsource (lib "eagle-import") (part "TPTP08R"))
    )
    (comp (ref "U15")
      (value "SKY13330-397LF")
      (footprint "eagle-import:QFN12")
      (libsource (lib "eagle-import") (part "SKYWORKS-13330397LF"))
    )
    (comp (ref "R14")
      (value "10k")
      (footprint "eagle-import:0603-RES")
      (fields (field (name "PARTNO") "RC0603JR-0710KL"))
      (libsource (lib "eagle-import") (part "RESISTOR0603-RES"))
    )
    (comp (ref "R15")
      (value "10k")
      (footprint "eagle-import:0603-RES")
      (fields (field (name "PARTNO") "RC0603JR-0710KL"))
      (libsource (lib "eagle-import") (part "RESISTOR0603-RES"))
    )
    (comp (ref "R16")
      (value "10k")
      (footprint "eagle-import:0603-RES")
      (fields (field (name "PARTNO") "RC0603JR-0710KL"))
      (libsource (lib "eagle-import") (part "RESISTOR0603-RES"))
    )
    (comp (ref "U8")
      (value "SE873Q5")
      (footprint "eagle-import:SE873")
      (libsource (lib "eagle-import") (part "SE873"))
    )
    (comp (ref "U9")
      (value "DMN63D8LDW")
      (footprint "eagle-import:SOT363")
      (fields (field (name "PARTNO") "DMN63D8LDW"))
      (libsource (lib "eagle-import") (part "DMN63D8LDW"))
    )
    (comp (ref "U10")
      (value "1575AT43A0040E")
      (footprint "eagle-import:1575AT43A0040E")
      (libsource (lib "eagle-import") (part "1575AT43A0040E"))
    )
    (comp (ref "C14")
      (value "22nF")
      (footprint "eagle-import:0603-CAP")
      (fields (field (name "PARTNO") "GRM188R71E223KA01D"))
      (libsource (lib "eagle-import") (part "CAP0603-CAP"))
    )
    (comp (ref "C15")
      (value "100pF")
      (footprint "eagle-import:0603-CAP")
      (fields (field (name "PARTNO") "GCM1885C2A101JA16D"))
      (libsource (lib "eagle-import") (part "CAP0603-CAP"))
    )
    (comp (ref "C16")
      (value "22nF")
      (footprint "eagle-import:0603-CAP")
      (fields (field (name "PARTNO") "GRM188R71E223KA01D"))
      (libsource (lib "eagle-import") (part "CAP0603-CAP"))
    )
    (comp (ref "C17")
      (value "100pF")
      (footprint "eagle-import:0603-CAP")
      (fields (field (name "PARTNO") "GCM1885C2A101JA16D"))
      (libsource (lib "eagle-import") (part "CAP0603-CAP"))
    )
    (comp (ref "C18")
      (value "7.5pF")
      (footprint "eagle-import:0603-CAP")
      (fields (field (name "PARTNO") "GRM1885C1H7R5DA01D"))
      (libsource (lib "eagle-import") (part "CAP0603-CAP"))
    )
    (comp (ref "C19")
      (value "13pF")
      (footprint "eagle-import:0603-CAP")
      (fields (field (name "PARTNO") "GRM1885C1H130JA01D"))
      (libsource (lib "eagle-import") (part "CAP0603-CAP"))
    )
    (comp (ref "C20")
      (value "7.5pF")
      (footprint "eagle-import:0603-CAP")
      (fields (field (name "PARTNO") "GRM1885C1H7R5DA01D"))
      (libsource (lib "eagle-import") (part "CAP0603-CAP"))
    )
    (comp (ref "C21")
      (value "470pF")
      (footprint "eagle-import:0603-CAP")
      (fields (field (name "PARTNO") "GCM1885C2A471JA16J"))
      (libsource (lib "eagle-import") (part "CAP0603-CAP"))
    )
    (comp (ref "C22")
      (value "20pF")
      (footprint "eagle-import:0603")
      (fields (field (name "PARTNO") "GRM1885C1H200JA01D"))
      (libsource (lib "eagle-import") (part "CAPACITOR0603"))
    )
    (comp (ref "C23")
      (value "16pF")
      (footprint "eagle-import:0603-CAP")
      (fields (field (name "PARTNO") "GCM1885C2A160JA16D"))
      (libsource (lib "eagle-import") (part "CAP0603-CAP"))
    )
    (comp (ref "C24")
      (value "24pF")
      (footprint "eagle-import:0603-CAP")
      (fields (field (name "PARTNO") "GCM1885C2A240JA16D"))
      (libsource (lib "eagle-import") (part "CAP0603-CAP"))
    )
    (comp (ref "C25")
      (value "24pF")
      (footprint "eagle-import:0603-CAP")
      (fields (field (name "PARTNO") "GCM1885C2A240JA16D"))
      (libsource (lib "eagle-import") (part "CAP0603-CAP"))
    )
    (comp (ref "C31")
      (value "13pF")
      (footprint "eagle-import:0603-CAP")
      (fields (field (name "PARTNO") "GRM1885C1H130JA01D"))
      (libsource (lib "eagle-import") (part "CAP0603-CAP"))
    )
    (comp (ref "C32")
      (value "2.2uF")
      (footprint "eagle-import:0603-CAP")
      (fields (field (name "PARTNO") "EMK107BJ225KA-T"))
      (libsource (lib "eagle-import") (part "CAP0603-CAP"))
    )
    (comp (ref "C34")
      (value "2.2uF")
      (footprint "eagle-import:0603-CAP")
      (fields (field (name "PARTNO") "EMK107BJ225KA-T"))
      (libsource (lib "eagle-import") (part "CAP0603-CAP"))
    )
    (comp (ref "L1")
      (value "47nH")
      (footprint "eagle-import:0603")
      (fields (field (name "PARTNO") "LQW18AS47NG00D"))
      (libsource (lib "eagle-import") (part "INDUCTOR0603"))
    )
    (comp (ref "L5")
      (value "470nH")
      (footprint "eagle-import:0603")
      (fields (field (name "PARTNO") "HK1608R47J-T"))
      (libsource (lib "eagle-import") (part "SparkFun-Passives_INDUCTOR0603"))
    )
    (comp (ref "L6")
      (value "130nH")
      (footprint "eagle-import:0603")
      (fields (field (name "PARTNO") "LQW18ANR13G00D"))
      (libsource (lib "eagle-import") (part "INDUCTOR0603"))
    )
    (comp (ref "L7")
      (value "100nH")
      (footprint "eagle-import:0603")
      (fields (field (name "PARTNO") "LQW18ANR10G00D"))
      (libsource (lib "eagle-import") (part "INDUCTOR0603"))
    )
    (comp (ref "L8")
      (value "200nH")
      (footprint "eagle-import:0603")
      (fields (field (name "PARTNO") "LQW18ANR20J00D"))
      (libsource (lib "eagle-import") (part "SparkFun-Passives_INDUCTOR0603"))
    )
    (comp (ref "L11")
      (value "56nH")
      (footprint "eagle-import:0603")
      (fields (field (name "PARTNO") "LQW18AN56NG00D"))
      (libsource (lib "eagle-import") (part "INDUCTOR0603"))
    )
    (comp (ref "L13")
      (value "200nH")
      (footprint "eagle-import:0603")
      (fields (field (name "PARTNO") "LQW18ANR20J00D"))
      (libsource (lib "eagle-import") (part "SparkFun-Passives_INDUCTOR0603"))
    )
    (comp (ref "R22")
      (value "22")
      (footprint "eagle-import:0603-RES")
      (fields (field (name "PARTNO") "RC0603JR-0722RL"))
      (libsource (lib "eagle-import") (part "RESISTOR0603-RES"))
    )
    (comp (ref "U11")
      (value "SI4463")
      (footprint "eagle-import:SI4463")
      (fields (field (name "PARTNO") "SI4463-C2A-GMR"))
      (libsource (lib "eagle-import") (part "SI4463"))
    )
    (comp (ref "U12")
      (value "SI4463")
      (footprint "eagle-import:SI4463")
      (fields (field (name "PARTNO") "SI4463-C2A-GMR"))
      (libsource (lib "eagle-import") (part "SI4463"))
    )
    (comp (ref "X1")
      (value "CX3225SB30000D0FPLCC")
      (footprint "eagle-import:NX3225")
      (libsource (lib "eagle-import") (part "XTAL-4-3225"))
    )
    (comp (ref "X2")
      (value "CX3225SB30000D0FPLCC")
      (footprint "eagle-import:NX3225")
      (libsource (lib "eagle-import") (part "XTAL-4-3225"))
    )
  )
  (nets
    (net (code "1") (name "1V8") (class "Default")
      (node (ref "1V8") (pin "TP") (pinfunction "TP_TP") (pintype "input"))
      (node (ref "C9") (pin "1") (pinfunction "1_1") (pintype "passive"))
      (node (ref "R14") (pin "2") (pinfunction "2_2") (pintype "passive"))
      (node (ref "R15") (pin "2") (pinfunction "2_2") (pintype "passive"))
      (node (ref "R19") (pin "2") (pinfunction "2_2") (pintype "passive"))
      (node (ref "U15") (pin "P$8") (pinfunction "EN_P$8") (pintype "bidirectional"))
      (node (ref "U4") (pin "6") (pinfunction "D_6") (pintype "bidirectional"))
      (node (ref "U5") (pin "5") (pinfunction "OUT_5") (pintype "passive"))
      (node (ref "U8") (pin "P$19") (pinfunction "V18_P$19") (pintype "bidirectional"))
      (node (ref "U8") (pin "P$3") (pinfunction "V18_P$3") (pintype "bidirectional"))
      (node (ref "U9") (pin "2") (pinfunction "G_2") (pintype "bidirectional"))
    )
    (net (code "2") (name "3.3V") (class "Default")
      (node (ref "3V3") (pin "TP") (pinfunction "TP_TP") (pintype "input"))
      (node (ref "C1") (pin "1") (pinfunction "1_1") (pintype "passive"))
      (node (ref "C12") (pin "1") (pinfunction "1_1") (pintype "passive"))
      (node (ref "C14") (pin "1") (pinfunction "1_1") (pintype "passive"))
      (node (ref "C15") (pin "1") (pinfunction "1_1") (pintype "passive"))
      (node (ref "C16") (pin "1") (pinfunction "1_1") (pintype "passive"))
      (node (ref "C17") (pin "1") (pinfunction "1_1") (pintype "passive"))
      (node (ref "C26") (pin "1") (pinfunction "1_1") (pintype "passive"))
      (node (ref "C27") (pin "1") (pinfunction "1_1") (pintype "passive"))
      (node (ref "C28") (pin "1") (pinfunction "1_1") (pintype "passive"))
      (node (ref "C32") (pin "1") (pinfunction "1_1") (pintype "passive"))
      (node (ref "C34") (pin "1") (pinfunction "1_1") (pintype "passive"))
      (node (ref "C45") (pin "1") (pinfunction "1_1") (pintype "passive"))
      (node (ref "C46") (pin "1") (pinfunction "1_1") (pintype "passive"))
      (node (ref "C48") (pin "1") (pinfunction "1_1") (pintype "passive"))
      (node (ref "C5") (pin "1") (pinfunction "1_1") (pintype "passive"))
      (node (ref "C8") (pin "1") (pinfunction "1_1") (pintype "passive"))
      (node (ref "JLINK") (pin "5") (pinfunction "5_5") (pintype "passive"))
      (node (ref "L12") (pin "P$2") (pinfunction "P$2_P$2") (pintype "bidirectional"))
      (node (ref "R1") (pin "2") (pinfunction "2_2") (pintype "passive"))
      (node (ref "R16") (pin "2") (pinfunction "2_2") (pintype "passive"))
      (node (ref "R22") (pin "2") (pinfunction "2_2") (pintype "passive"))
      (node (ref "R6") (pin "1") (pinfunction "1_1") (pintype "passive"))
      (node (ref "U11") (pin "6") (pinfunction "VDD_1_6") (pintype "power_in"))
      (node (ref "U11") (pin "8") (pinfunction "VDD_2_8") (pintype "power_in"))
      (node (ref "U12") (pin "6") (pinfunction "VDD_1_6") (pintype "power_in"))
      (node (ref "U12") (pin "8") (pinfunction "VDD_2_8") (pintype "power_in"))
      (node (ref "U13") (pin "1") (pinfunction "VDD_1") (pintype "bidirectional"))
      (node (ref "U13") (pin "17") (pinfunction "VDD_17") (pintype "bidirectional"))
      (node (ref "U13") (pin "5") (pinfunction "VDDA_5") (pintype "bidirectional"))
      (node (ref "U15") (pin "P$9") (pinfunction "VCC_P$9") (pintype "bidirectional"))
      (node (ref "U5") (pin "1") (pinfunction "IN_1") (pintype "input"))
      (node (ref "U5") (pin "3") (pinfunction "EN_3") (pintype "input"))
      (node (ref "U6") (pin "4") (pinfunction "VCC_4") (pintype "bidirectional"))
    )
    (net (code "3") (name "BOOT0") (class "Default")
      (node (ref "C38") (pin "1") (pinfunction "1_1") (pintype "passive"))
      (node (ref "R23") (pin "1") (pinfunction "1_1") (pintype "passive"))
      (node (ref "R3") (pin "1") (pinfunction "1_1") (pintype "passive"))
      (node (ref "U13") (pin "31") (pinfunction "BOOT0_31") (pintype "bidirectional"))
    )
    (net (code "4") (name "BOOT_CTRL") (class "Default")
      (node (ref "R3") (pin "2") (pinfunction "2_2") (pintype "passive"))
      (node (ref "U13") (pin "18") (pinfunction "PA8_18") (pintype "bidirectional"))
    )
    (net (code "5") (name "CS1") (class "Default")
      (node (ref "U11") (pin "15") (pinfunction "NSEL_15") (pintype "input"))
      (node (ref "U13") (pin "10") (pinfunction "PA4_10") (pintype "bidirectional"))
    )
    (net (code "6") (name "CS2") (class "Default")
      (node (ref "U12") (pin "15") (pinfunction "NSEL_15") (pintype "input"))
      (node (ref "U13") (pin "6") (pinfunction "PA0_6") (pintype "bidirectional"))
    )
    (net (code "7") (name "GND") (class "Default")
      (node (ref "C1") (pin "2") (pinfunction "2_2") (pintype "passive"))
      (node (ref "C11") (pin "2") (pinfunction "2_2") (pintype "passive"))
      (node (ref "C12") (pin "2") (pinfunction "2_2") (pintype "passive"))
      (node (ref "C13") (pin "1") (pinfunction "1_1") (pintype "passive"))
      (node (ref "C14") (pin "2") (pinfunction "2_2") (pintype "passive"))
      (node (ref "C15") (pin "2") (pinfunction "2_2") (pintype "passive"))
      (node (ref "C16") (pin "2") (pinfunction "2_2") (pintype "passive"))
      (node (ref "C17") (pin "2") (pinfunction "2_2") (pintype "passive"))
      (node (ref "C19") (pin "1") (pinfunction "1_1") (pintype "passive"))
      (node (ref "C21") (pin "2") (pinfunction "2_2") (pintype "passive"))
      (node (ref "C23") (pin "2") (pinfunction "2_2") (pintype "passive"))
      (node (ref "C24") (pin "2") (pinfunction "2_2") (pintype "passive"))
      (node (ref "C25") (pin "2") (pinfunction "2_2") (pintype "passive"))
      (node (ref "C26") (pin "2") (pinfunction "2_2") (pintype "passive"))
      (node (ref "C27") (pin "2") (pinfunction "2_2") (pintype "passive"))
      (node (ref "C28") (pin "2") (pinfunction "2_2") (pintype "passive"))
      (node (ref "C3") (pin "2") (pinfunction "2_2") (pintype "passive"))
      (node (ref "C30") (pin "2") (pinfunction "2_2") (pintype "passive"))
      (node (ref "C31") (pin "1") (pinfunction "1_1") (pintype "passive"))
      (node (ref "C32") (pin "2") (pinfunction "2_2") (pintype "passive"))
      (node (ref "C33") (pin "1") (pinfunction "1_1") (pintype "passive"))
      (node (ref "C34") (pin "2") (pinfunction "2_2") (pintype "passive"))
      (node (ref "C36") (pin "2") (pinfunction "2_2") (pintype "passive"))
      (node (ref "C37") (pin "2") (pinfunction "2_2") (pintype "passive"))
      (node (ref "C38") (pin "2") (pinfunction "2_2") (pintype "passive"))
      (node (ref "C39") (pin "2") (pinfunction "2_2") (pintype "passive"))
      (node (ref "C4") (pin "2") (pinfunction "22_2") (pintype "passive"))
      (node (ref "C41") (pin "2") (pinfunction "2_2") (pintype "passive"))
      (node (ref "C42") (pin "2") (pinfunction "2_2") (pintype "passive"))
      (node (ref "C43") (pin "2") (pinfunction "2_2") (pintype "passive"))
      (node (ref "C45") (pin "2") (pinfunction "2_2") (pintype "passive"))
      (node (ref "C46") (pin "2") (pinfunction "2_2") (pintype "passive"))
      (node (ref "C47") (pin "2") (pinfunction "2_2") (pintype "passive"))
      (node (ref "C48") (pin "2") (pinfunction "2_2") (pintype "passive"))
      (node (ref "C49") (pin "2") (pinfunction "2_2") (pintype "passive"))
      (node (ref "C5") (pin "2") (pinfunction "2_2") (pintype "passive"))
      (node (ref "C52") (pin "2") (pinfunction "2_2") (pintype "passive"))
      (node (ref "C53") (pin "2") (pinfunction "2_2") (pintype "passive"))
      (node (ref "C6") (pin "2") (pinfunction "2_2") (pintype "passive"))
      (node (ref "C7") (pin "2") (pinfunction "2_2") (pintype "passive"))
      (node (ref "C8") (pin "2") (pinfunction "2_2") (pintype "passive"))
      (node (ref "C9") (pin "2") (pinfunction "2_2") (pintype "passive"))
      (node (ref "D1") (pin "A") (pinfunction "A_A") (pintype "passive"))
      (node (ref "GND1") (pin "TP") (pinfunction "TP_TP") (pintype "input"))
      (node (ref "GND2") (pin "TP") (pinfunction "TP_TP") (pintype "input"))
      (node (ref "J$1") (pin "GND@0") (pinfunction "GND_GND@0") (pintype "bidirectional"))
      (node (ref "J$1") (pin "GND@1") (pinfunction "GND_GND@1") (pintype "bidirectional"))
      (node (ref "J$1") (pin "GND@2") (pinfunction "GND_GND@2") (pintype "bidirectional"))
      (node (ref "J$1") (pin "GND@3") (pinfunction "GND_GND@3") (pintype "bidirectional"))
      (node (ref "JLINK") (pin "1") (pinfunction "1_1") (pintype "passive"))
      (node (ref "JP1") (pin "7") (pinfunction "7_7") (pintype "bidirectional"))
      (node (ref "JP1") (pin "8") (pinfunction "8_8") (pintype "bidirectional"))
      (node (ref "L16") (pin "1") (pinfunction "1_1") (pintype "passive"))
      (node (ref "L22") (pin "1") (pinfunction "1_1") (pintype "passive"))
      (node (ref "R10") (pin "1") (pinfunction "1_1") (pintype "passive"))
      (node (ref "R12") (pin "1") (pinfunction "1_1") (pintype "passive"))
      (node (ref "R2") (pin "1") (pinfunction "1_1") (pintype "passive"))
      (node (ref "R23") (pin "2") (pinfunction "2_2") (pintype "passive"))
      (node (ref "R4") (pin "1") (pinfunction "1_1") (pintype "passive"))
      (node (ref "R9") (pin "1") (pinfunction "1_1") (pintype "passive"))
      (node (ref "S1") (pin "P$2") (pinfunction "S2_P$2") (pintype "bidirectional"))
      (node (ref "TP2") (pin "TP") (pinfunction "TP_TP") (pintype "input"))
      (node (ref "TP3") (pin "TP") (pinfunction "TP_TP") (pintype "input"))
      (node (ref "TP4") (pin "TP") (pinfunction "TP_TP") (pintype "input"))
      (node (ref "TP5") (pin "TP") (pinfunction "TP_TP") (pintype "input"))
      (node (ref "TP6") (pin "TP") (pinfunction "TP_TP") (pintype "input"))
      (node (ref "TP7") (pin "TP") (pinfunction "TP_TP") (pintype "input"))
      (node (ref "TP8") (pin "TP") (pinfunction "TP_TP") (pintype "input"))
      (node (ref "TP9") (pin "TP") (pinfunction "TP_TP") (pintype "input"))
      (node (ref "U1") (pin "2") (pinfunction "GND_2") (pintype "bidirectional"))
      (node (ref "U11") (pin "EXP") (pinfunction "PAD_EXP") (pintype "bidirectional"))
      (node (ref "U12") (pin "EXP") (pinfunction "PAD_EXP") (pintype "bidirectional"))
      (node (ref "U13") (pin "16") (pinfunction "VSS_16") (pintype "bidirectional"))
      (node (ref "U13") (pin "32") (pinfunction "VSS_32") (pintype "bidirectional"))
      (node (ref "U13") (pin "EXP") (pinfunction "PAD_EXP") (pintype "bidirectional"))
      (node (ref "U15") (pin "P$1") (pinfunction "GND_P$1") (pintype "bidirectional"))
      (node (ref "U15") (pin "P$10") (pinfunction "GND_P$10") (pintype "bidirectional"))
      (node (ref "U15") (pin "P$12") (pinfunction "GND_P$12") (pintype "bidirectional"))
      (node (ref "U15") (pin "P$13") (pinfunction "GND_P$13") (pintype "bidirectional"))
      (node (ref "U15") (pin "P$3") (pinfunction "GND_P$3") (pintype "bidirectional"))
      (node (ref "U15") (pin "P$4") (pinfunction "GND_P$4") (pintype "bidirectional"))
      (node (ref "U15") (pin "P$6") (pinfunction "GND_P$6") (pintype "bidirectional"))
      (node (ref "U3") (pin "P$4") (pinfunction "GND_P$4") (pintype "bidirectional"))
      (node (ref "U3") (pin "P$7") (pinfunction "GND_P$7") (pintype "bidirectional"))
      (node (ref "U4") (pin "4") (pinfunction "S_4") (pintype "bidirectional"))
      (node (ref "U5") (pin "2") (pinfunction "GND_2") (pintype "input"))
      (node (ref "U6") (pin "2") (pinfunction "GND_2") (pintype "bidirectional"))
      (node (ref "U7") (pin "2") (pinfunction "S_2") (pintype "passive"))
      (node (ref "U7") (pin "2@1") (pinfunction "PAD_2@1") (pintype "bidirectional"))
      (node (ref "U8") (pin "P$10") (pinfunction "GND_P$10") (pintype "bidirectional"))
      (node (ref "U8") (pin "P$2") (pinfunction "GND_P$2") (pintype "bidirectional"))
      (node (ref "U8") (pin "P$20") (pinfunction "GND_P$20") (pintype "bidirectional"))
      (node (ref "U9") (pin "4") (pinfunction "S_4") (pintype "bidirectional"))
      (node (ref "X1") (pin "2") (pinfunction "G2_2") (pintype "power_in"))
      (node (ref "X1") (pin "4") (pinfunction "G1_4") (pintype "power_in"))
      (node (ref "X2") (pin "2") (pinfunction "G2_2") (pintype "power_in"))
      (node (ref "X2") (pin "4") (pinfunction "G1_4") (pintype "power_in"))
    )
    (net (code "8") (name "GNSS_1PPS") (class "Default")
      (node (ref "U8") (pin "P$11") (pinfunction "TM_P$11") (pintype "bidirectional"))
      (node (ref "U9") (pin "5") (pinfunction "G_5") (pintype "bidirectional"))
    )
    (net (code "9") (name "GNSS_EN") (class "Default")
      (node (ref "R9") (pin "2") (pinfunction "2_2") (pintype "passive"))
      (node (ref "U13") (pin "2") (pinfunction "OSC_IN/PC14_2") (pintype "bidirectional"))
      (node (ref "U4") (pin "2") (pinfunction "G_2") (pintype "bidirectional"))
    )
    (net (code "10") (name "GNSS_EN_1V8") (class "Default")
      (node (ref "R10") (pin "2") (pinfunction "2_2") (pintype "passive"))
      (node (ref "U4") (pin "1") (pinfunction "S_1") (pintype "bidirectional"))
      (node (ref "U8") (pin "P$6") (pinfunction "ON_OFF_P$6") (pintype "bidirectional"))
    )
    (net (code "11") (name "GNSS_UART_TX") (class "Default")
      (node (ref "R15") (pin "1") (pinfunction "1_1") (pintype "passive"))
      (node (ref "U8") (pin "P$15") (pinfunction "TX_P$15") (pintype "bidirectional"))
      (node (ref "U9") (pin "1") (pinfunction "S_1") (pintype "bidirectional"))
    )
    (net (code "12") (name "I2C_SCL") (class "Default")
      (node (ref "U13") (pin "29") (pinfunction "PB6_29") (pintype "bidirectional"))
      (node (ref "U6") (pin "1") (pinfunction "SCL_1") (pintype "bidirectional"))
    )
    (net (code "13") (name "I2C_SDA") (class "Default")
      (node (ref "U13") (pin "30") (pinfunction "PB7_30") (pintype "bidirectional"))
      (node (ref "U6") (pin "3") (pinfunction "SDA_3") (pintype "bidirectional"))
    )
    (net (code "14") (name "MCU_GNSS_1PPS") (class "Default")
      (node (ref "U13") (pin "8") (pinfunction "PA2_8") (pintype "bidirectional"))
      (node (ref "U9") (pin "3") (pinfunction "D_3") (pintype "bidirectional"))
    )
    (net (code "15") (name "MCU_GNSS_UART_RX") (class "Default")
      (node (ref "R16") (pin "1") (pinfunction "1_1") (pintype "passive"))
      (node (ref "U13") (pin "9") (pinfunction "PA3_9") (pintype "bidirectional"))
      (node (ref "U9") (pin "6") (pinfunction "D_6") (pintype "bidirectional"))
    )
    (net (code "16") (name "MCU_UART_RX") (class "Default")
      (node (ref "JP1") (pin "3") (pinfunction "3_3") (pintype "bidirectional"))
      (node (ref "RX") (pin "TP") (pinfunction "TP_TP") (pintype "input"))
      (node (ref "U13") (pin "20") (pinfunction "PA10_20") (pintype "bidirectional"))
    )
    (net (code "17") (name "MCU_UART_TX") (class "Default")
      (node (ref "JP1") (pin "6") (pinfunction "6_6") (pintype "bidirectional"))
      (node (ref "TX") (pin "TP") (pinfunction "TP_TP") (pintype "input"))
      (node (ref "U13") (pin "19") (pinfunction "PA9_19") (pintype "bidirectional"))
    )
    (net (code "18") (name "MISO") (class "Default")
      (node (ref "U11") (pin "13") (pinfunction "SDO_13") (pintype "output"))
      (node (ref "U12") (pin "13") (pinfunction "SDO_13") (pintype "output"))
      (node (ref "U13") (pin "12") (pinfunction "PA6_12") (pintype "bidirectional"))
    )
    (net (code "19") (name "MOSI") (class "Default")
      (node (ref "U11") (pin "14") (pinfunction "SDI_14") (pintype "input"))
      (node (ref "U12") (pin "14") (pinfunction "SDI_14") (pintype "input"))
      (node (ref "U13") (pin "13") (pinfunction "PA7_13") (pintype "bidirectional"))
    )
    (net (code "20") (name "NRST") (class "Default")
      (node (ref "JLINK") (pin "2") (pinfunction "2_2") (pintype "passive"))
      (node (ref "NRST") (pin "TP") (pinfunction "TP_TP") (pintype "input"))
      (node (ref "S1") (pin "P$1") (pinfunction "S1_P$1") (pintype "bidirectional"))
      (node (ref "U13") (pin "4") (pinfunction "NRST_4") (pintype "bidirectional"))
    )
    (net (code "21") (name "Net-(C4-11)") (class "Default")
      (node (ref "C4") (pin "1") (pinfunction "11_1") (pintype "passive"))
      (node (ref "C43") (pin "1") (pinfunction "1_1") (pintype "passive"))
      (node (ref "L2") (pin "P$1") (pinfunction "P$1_P$1") (pintype "bidirectional"))
      (node (ref "U1") (pin "4") (pinfunction "EN_4") (pintype "bidirectional"))
      (node (ref "U1") (pin "5") (pinfunction "IN_5") (pintype "bidirectional"))
    )
    (net (code "22") (name "Net-(C10-Pad1)") (class "Default")
      (node (ref "C10") (pin "1") (pinfunction "1_1") (pintype "passive"))
      (node (ref "C13") (pin "2") (pinfunction "2_2") (pintype "passive"))
      (node (ref "L14") (pin "1") (pinfunction "1_1") (pintype "passive"))
      (node (ref "L22") (pin "2") (pinfunction "2_2") (pintype "passive"))
    )
    (net (code "23") (name "Net-(C10-Pad2)") (class "Default")
      (node (ref "C10") (pin "2") (pinfunction "2_2") (pintype "passive"))
      (node (ref "L21") (pin "2") (pinfunction "2_2") (pintype "passive"))
    )
    (net (code "24") (name "Net-(C11-Pad1)") (class "Default")
      (node (ref "C11") (pin "1") (pinfunction "1_1") (pintype "passive"))
      (node (ref "L17") (pin "P$2") (pinfunction "P$2_P$2") (pintype "bidirectional"))
      (node (ref "R11") (pin "1") (pinfunction "1_1") (pintype "passive"))
      (node (ref "R12") (pin "2") (pinfunction "2_2") (pintype "passive"))
    )
    (net (code "25") (name "Net-(C21-Pad1)") (class "Default")
      (node (ref "C21") (pin "1") (pinfunction "1_1") (pintype "passive"))
      (node (ref "L5") (pin "1") (pinfunction "1_1") (pintype "passive"))
      (node (ref "R22") (pin "1") (pinfunction "1_1") (pintype "passive"))
    )
    (net (code "26") (name "Net-(C22-PadP$2)") (class "Default")
      (node (ref "C22") (pin "P$2") (pinfunction "P$2_P$2") (pintype "bidirectional"))
      (node (ref "L1") (pin "P$1") (pinfunction "P$1_P$1") (pintype "bidirectional"))
    )
    (net (code "27") (name "Net-(C23-Pad1)") (class "Default")
      (node (ref "C23") (pin "1") (pinfunction "1_1") (pintype "passive"))
      (node (ref "L1") (pin "P$2") (pinfunction "P$2_P$2") (pintype "bidirectional"))
      (node (ref "L6") (pin "P$1") (pinfunction "P$1_P$1") (pintype "bidirectional"))
    )
    (net (code "28") (name "Net-(C24-Pad1)") (class "Default")
      (node (ref "C24") (pin "1") (pinfunction "1_1") (pintype "passive"))
      (node (ref "L6") (pin "P$2") (pinfunction "P$2_P$2") (pintype "bidirectional"))
      (node (ref "L7") (pin "P$1") (pinfunction "P$1_P$1") (pintype "bidirectional"))
    )
    (net (code "29") (name "Net-(C25-Pad1)") (class "Default")
      (node (ref "C25") (pin "1") (pinfunction "1_1") (pintype "passive"))
      (node (ref "L11") (pin "P$1") (pinfunction "P$1_P$1") (pintype "bidirectional"))
      (node (ref "L7") (pin "P$2") (pinfunction "P$2_P$2") (pintype "bidirectional"))
    )
    (net (code "30") (name "Net-(C29-Pad2)") (class "Default")
      (node (ref "C29") (pin "2") (pinfunction "2_2") (pintype "passive"))
      (node (ref "C30") (pin "1") (pinfunction "1_1") (pintype "passive"))
      (node (ref "L3") (pin "P$1") (pinfunction "P$1_P$1") (pintype "bidirectional"))
    )
    (net (code "31") (name "Net-(C33-Pad2)") (class "Default")
      (node (ref "C33") (pin "2") (pinfunction "2_2") (pintype "passive"))
      (node (ref "C35") (pin "1") (pinfunction "1_1") (pintype "passive"))
      (node (ref "C40") (pin "2") (pinfunction "2_2") (pintype "passive"))
      (node (ref "L16") (pin "2") (pinfunction "2_2") (pintype "passive"))
    )
    (net (code "32") (name "Net-(C35-Pad2)") (class "Default")
      (node (ref "C35") (pin "2") (pinfunction "2_2") (pintype "passive"))
      (node (ref "L14") (pin "2") (pinfunction "2_2") (pintype "passive"))
    )
    (net (code "33") (name "Net-(C36-Pad1)") (class "Default")
      (node (ref "C36") (pin "1") (pinfunction "1_1") (pintype "passive"))
      (node (ref "L10") (pin "1") (pinfunction "1_1") (pintype "passive"))
      (node (ref "L9") (pin "2") (pinfunction "2_2") (pintype "passive"))
    )
    (net (code "34") (name "Net-(C40-Pad1)") (class "Default")
      (node (ref "C40") (pin "1") (pinfunction "1_1") (pintype "passive"))
      (node (ref "L15") (pin "1") (pinfunction "1_1") (pintype "passive"))
    )
    (net (code "35") (name "Net-(C42-Pad1)") (class "Default")
      (node (ref "C42") (pin "1") (pinfunction "1_1") (pintype "passive"))
      (node (ref "C52") (pin "1") (pinfunction "1_1") (pintype "passive"))
      (node (ref "L10") (pin "2") (pinfunction "2_2") (pintype "passive"))
      (node (ref "L23") (pin "P$1") (pinfunction "P$1_P$1") (pintype "bidirectional"))
    )
    (net (code "36") (name "Net-(C44-Pad1)") (class "Default")
      (node (ref "C44") (pin "1") (pinfunction "1_1") (pintype "passive"))
      (node (ref "C53") (pin "1") (pinfunction "1_1") (pintype "passive"))
      (node (ref "L23") (pin "P$2") (pinfunction "P$2_P$2") (pintype "bidirectional"))
    )
    (net (code "37") (name "Net-(D2-PadA)") (class "Default")
      (node (ref "D2") (pin "A") (pinfunction "A_A") (pintype "passive"))
      (node (ref "JP1") (pin "1") (pinfunction "1_1") (pintype "bidirectional"))
      (node (ref "JP1") (pin "2") (pinfunction "2_2") (pintype "bidirectional"))
      (node (ref "V_IN") (pin "TP") (pinfunction "TP_TP") (pintype "input"))
    )
    (net (code "38") (name "Net-(D2-PadC)") (class "Default")
      (node (ref "D2") (pin "C") (pinfunction "C_C") (pintype "passive"))
      (node (ref "F1") (pin "1") (pinfunction "1_1") (pintype "passive"))
    )
    (net (code "39") (name "Net-(J$1-SIGNAL)") (class "Default")
      (node (ref "J$1") (pin "SIG") (pinfunction "SIGNAL_SIG") (pintype "bidirectional"))
      (node (ref "TP1") (pin "TP") (pinfunction "TP_TP") (pintype "input"))
      (node (ref "U15") (pin "P$2") (pinfunction "RF1_P$2") (pintype "bidirectional"))
    )
    (net (code "40") (name "Net-(U1-BS)") (class "Default")
      (node (ref "C2") (pin "1") (pinfunction "1_1") (pintype "passive"))
      (node (ref "U1") (pin "1") (pinfunction "BS_1") (pintype "bidirectional"))
    )
    (net (code "41") (name "Net-(U1-FB)") (class "Default")
      (node (ref "R1") (pin "1") (pinfunction "1_1") (pintype "passive"))
      (node (ref "R2") (pin "2") (pinfunction "2_2") (pintype "passive"))
      (node (ref "U1") (pin "3") (pinfunction "FB_3") (pintype "bidirectional"))
    )
    (net (code "42") (name "Net-(U1-SW)") (class "Default")
      (node (ref "C2") (pin "2") (pinfunction "2_2") (pintype "passive"))
      (node (ref "D1") (pin "C") (pinfunction "C_C") (pintype "passive"))
      (node (ref "L12") (pin "P$1") (pinfunction "P$1_P$1") (pintype "bidirectional"))
      (node (ref "U1") (pin "6") (pinfunction "SW_6") (pintype "bidirectional"))
    )
    (net (code "43") (name "Net-(U3-ADJ)") (class "Default")
      (node (ref "R4") (pin "2") (pinfunction "2_2") (pintype "passive"))
      (node (ref "R5") (pin "1") (pinfunction "1_1") (pintype "passive"))
      (node (ref "U3") (pin "P$2") (pinfunction "ADJ_P$2") (pintype "bidirectional"))
    )
    (net (code "44") (name "Net-(U7-D)") (class "Default")
      (node (ref "C37") (pin "1") (pinfunction "1_1") (pintype "passive"))
      (node (ref "C39") (pin "1") (pinfunction "1_1") (pintype "passive"))
      (node (ref "L4") (pin "2") (pinfunction "2_2") (pintype "passive"))
      (node (ref "L9") (pin "1") (pinfunction "1_1") (pintype "passive"))
      (node (ref "U7") (pin "3") (pinfunction "D_3") (pintype "passive"))
    )
    (net (code "45") (name "Net-(U7-G)") (class "Default")
      (node (ref "L17") (pin "P$1") (pinfunction "P$1_P$1") (pintype "bidirectional"))
      (node (ref "L3") (pin "P$2") (pinfunction "P$2_P$2") (pintype "bidirectional"))
      (node (ref "U7") (pin "1") (pinfunction "G_1") (pintype "passive"))
    )
    (net (code "46") (name "Net-(U8-GPIO6)") (class "Default")
      (node (ref "R14") (pin "1") (pinfunction "1_1") (pintype "passive"))
      (node (ref "U8") (pin "P$13") (pinfunction "GPIO6_P$13") (pintype "bidirectional"))
    )
    (net (code "47") (name "Net-(U10-RF)") (class "Default")
      (node (ref "U10") (pin "P$1") (pinfunction "RF_P$1") (pintype "bidirectional"))
      (node (ref "U8") (pin "P$1") (pinfunction "RF_IN_P$1") (pintype "bidirectional"))
    )
    (net (code "48") (name "Net-(U11-RXN)") (class "Default")
      (node (ref "C19") (pin "2") (pinfunction "2_2") (pintype "passive"))
      (node (ref "L8") (pin "2") (pinfunction "2_2") (pintype "passive"))
      (node (ref "U11") (pin "3") (pinfunction "RXN_3") (pintype "input"))
    )
    (net (code "49") (name "Net-(U11-RXP)") (class "Default")
      (node (ref "C18") (pin "1") (pinfunction "1_1") (pintype "passive"))
      (node (ref "L8") (pin "1") (pinfunction "1_1") (pintype "passive"))
      (node (ref "U11") (pin "2") (pinfunction "RXP_2") (pintype "input"))
    )
    (net (code "50") (name "Net-(U11-TX)") (class "Default")
      (node (ref "C22") (pin "P$1") (pinfunction "P$1_P$1") (pintype "bidirectional"))
      (node (ref "L5") (pin "2") (pinfunction "2_2") (pintype "passive"))
      (node (ref "U11") (pin "4") (pinfunction "TX_4") (pintype "output"))
    )
    (net (code "51") (name "Net-(U11-XIN)") (class "Default")
      (node (ref "U11") (pin "17") (pinfunction "XIN_17") (pintype "input"))
      (node (ref "X1") (pin "3") (pinfunction "X2_3") (pintype "bidirectional"))
    )
    (net (code "52") (name "Net-(U11-XOUT)") (class "Default")
      (node (ref "U11") (pin "16") (pinfunction "XOUT_16") (pintype "bidirectional"))
      (node (ref "X1") (pin "1") (pinfunction "X1_1") (pintype "bidirectional"))
    )
    (net (code "53") (name "Net-(U12-RXN)") (class "Default")
      (node (ref "C31") (pin "2") (pinfunction "2_2") (pintype "passive"))
      (node (ref "L13") (pin "2") (pinfunction "2_2") (pintype "passive"))
      (node (ref "U12") (pin "3") (pinfunction "RXN_3") (pintype "input"))
    )
    (net (code "54") (name "Net-(U12-RXP)") (class "Default")
      (node (ref "C20") (pin "1") (pinfunction "1_1") (pintype "passive"))
      (node (ref "L13") (pin "1") (pinfunction "1_1") (pintype "passive"))
      (node (ref "U12") (pin "2") (pinfunction "RXP_2") (pintype "input"))
    )
    (net (code "55") (name "Net-(U12-XIN)") (class "Default")
      (node (ref "U12") (pin "17") (pinfunction "XIN_17") (pintype "input"))
      (node (ref "X2") (pin "3") (pinfunction "X2_3") (pintype "bidirectional"))
    )
    (net (code "56") (name "Net-(U12-XOUT)") (class "Default")
      (node (ref "U12") (pin "16") (pinfunction "XOUT_16") (pintype "bidirectional"))
      (node (ref "X2") (pin "1") (pinfunction "X1_1") (pintype "bidirectional"))
    )
    (net (code "57") (name "PA_IN") (class "Default")
      (node (ref "C29") (pin "1") (pinfunction "1_1") (pintype "passive"))
      (node (ref "L11") (pin "P$2") (pinfunction "P$2_P$2") (pintype "bidirectional"))
    )
    (net (code "58") (name "PA_OUT") (class "Default")
      (node (ref "C44") (pin "2") (pinfunction "2_2") (pintype "passive"))
      (node (ref "U15") (pin "P$5") (pinfunction "RF3_P$5") (pintype "bidirectional"))
    )
    (net (code "59") (name "RF_IN") (class "Default")
      (node (ref "L21") (pin "1") (pinfunction "1_1") (pintype "passive"))
      (node (ref "U15") (pin "P$11") (pinfunction "RF2_P$11") (pintype "bidirectional"))
    )
    (net (code "60") (name "RX_EN") (class "Default")
      (node (ref "R19") (pin "1") (pinfunction "1_1") (pintype "passive"))
      (node (ref "U15") (pin "P$7") (pinfunction "CTRL_P$7") (pintype "bidirectional"))
      (node (ref "U4") (pin "3") (pinfunction "D_3") (pintype "bidirectional"))
    )
    (net (code "61") (name "RX_IC_CLK") (class "Default")
      (node (ref "U12") (pin "20") (pinfunction "GPIO3_20") (pintype "bidirectional"))
      (node (ref "U13") (pin "26") (pinfunction "PB3_26") (pintype "bidirectional"))
    )
    (net (code "62") (name "RX_IC_DATA") (class "Default")
      (node (ref "U12") (pin "10") (pinfunction "GPIO1_10") (pintype "bidirectional"))
      (node (ref "U13") (pin "27") (pinfunction "PB4_27") (pintype "bidirectional"))
    )
    (net (code "63") (name "RX_IN") (class "Default")
      (node (ref "C18") (pin "2") (pinfunction "2_2") (pintype "passive"))
      (node (ref "C20") (pin "2") (pinfunction "2_2") (pintype "passive"))
      (node (ref "L15") (pin "2") (pinfunction "2_2") (pintype "passive"))
    )
    (net (code "64") (name "SCK") (class "Default")
      (node (ref "U11") (pin "12") (pinfunction "SCLK_12") (pintype "input"))
      (node (ref "U12") (pin "12") (pinfunction "SCLK_12") (pintype "input"))
      (node (ref "U13") (pin "11") (pinfunction "PA5_11") (pintype "bidirectional"))
    )
    (net (code "65") (name "SDN1") (class "Default")
      (node (ref "U11") (pin "1") (pinfunction "SDN_1") (pintype "input"))
      (node (ref "U13") (pin "14") (pinfunction "PB0_14") (pintype "bidirectional"))
    )
    (net (code "66") (name "SDN2") (class "Default")
      (node (ref "U12") (pin "1") (pinfunction "SDN_1") (pintype "input"))
      (node (ref "U13") (pin "25") (pinfunction "PA15_25") (pintype "bidirectional"))
    )
    (net (code "67") (name "SPARE") (class "Default")
      (node (ref "JP1") (pin "5") (pinfunction "5_5") (pintype "bidirectional"))
      (node (ref "U13") (pin "21") (pinfunction "PA11_21") (pintype "bidirectional"))
    )
    (net (code "68") (name "SWCLK") (class "Default")
      (node (ref "JLINK") (pin "3") (pinfunction "3_3") (pintype "passive"))
      (node (ref "SWCLK") (pin "TP") (pinfunction "TP_TP") (pintype "input"))
      (node (ref "U13") (pin "24") (pinfunction "PA14_24") (pintype "bidirectional"))
    )
    (net (code "69") (name "SWDIO") (class "Default")
      (node (ref "JLINK") (pin "4") (pinfunction "4_4") (pintype "passive"))
      (node (ref "SWDIO") (pin "TP") (pinfunction "TP_TP") (pintype "input"))
      (node (ref "U13") (pin "23") (pinfunction "PA13_23") (pintype "bidirectional"))
    )
    (net (code "70") (name "TRX_IC_CLOCK") (class "Default")
      (node (ref "U11") (pin "19") (pinfunction "GPIO2_19") (pintype "bidirectional"))
      (node (ref "U13") (pin "7") (pinfunction "PA1_7") (pintype "bidirectional"))
    )
    (net (code "71") (name "TRX_IC_DATA") (class "Default")
      (node (ref "U11") (pin "10") (pinfunction "GPIO1_10") (pintype "bidirectional"))
      (node (ref "U13") (pin "15") (pinfunction "PB1_15") (pintype "bidirectional"))
    )
    (net (code "72") (name "TX_CTRL") (class "Default")
      (node (ref "R11") (pin "2") (pinfunction "2_2") (pintype "passive"))
      (node (ref "U13") (pin "28") (pinfunction "PB5_28") (pintype "bidirectional"))
      (node (ref "U4") (pin "5") (pinfunction "G_5") (pintype "bidirectional"))
    )
    (net (code "73") (name "TX_DISABLE") (class "Default")
      (node (ref "JP1") (pin "4") (pinfunction "4_4") (pintype "bidirectional"))
      (node (ref "TX_OFF") (pin "TP") (pinfunction "TP_TP") (pintype "input"))
      (node (ref "U13") (pin "22") (pinfunction "PA12_22") (pintype "bidirectional"))
    )
    (net (code "74") (name "V_BAT") (class "Default")
      (node (ref "C3") (pin "1") (pinfunction "1_1") (pintype "passive"))
      (node (ref "C41") (pin "1") (pinfunction "1_1") (pintype "passive"))
      (node (ref "C47") (pin "1") (pinfunction "1_1") (pintype "passive"))
      (node (ref "C6") (pin "1") (pinfunction "1_1") (pintype "passive"))
      (node (ref "F1") (pin "2") (pinfunction "2_2") (pintype "passive"))
      (node (ref "L2") (pin "P$2") (pinfunction "P$2_P$2") (pintype "bidirectional"))
      (node (ref "U3") (pin "P$5") (pinfunction "EN_P$5") (pintype "bidirectional"))
      (node (ref "U3") (pin "P$6") (pinfunction "VIN_P$6") (pintype "bidirectional"))
    )
    (net (code "75") (name "V_PA") (class "Default")
      (node (ref "C49") (pin "1") (pinfunction "1_1") (pintype "passive"))
      (node (ref "C7") (pin "1") (pinfunction "1_1") (pintype "passive"))
      (node (ref "L4") (pin "1") (pinfunction "1_1") (pintype "passive"))
      (node (ref "R5") (pin "2") (pinfunction "2_2") (pintype "passive"))
      (node (ref "U3") (pin "P$1") (pinfunction "VOUT_P$1") (pintype "bidirectional"))
      (node (ref "V_PA") (pin "TP") (pinfunction "TP_TP") (pintype "input"))
    )
    (net (code "76") (name "unconnected-(S1-S1-PadP$4)") (class "Default")
      (node (ref "S1") (pin "P$4") (pinfunction "S1_P$4") (pintype "bidirectional"))
    )
    (net (code "77") (name "unconnected-(S1-S2-PadP$3)") (class "Default")
      (node (ref "S1") (pin "P$3") (pinfunction "S2_P$3") (pintype "bidirectional"))
    )
    (net (code "78") (name "unconnected-(U3-PG-PadP$3)") (class "Default")
      (node (ref "U3") (pin "P$3") (pinfunction "PG_P$3") (pintype "bidirectional"))
    )
    (net (code "79") (name "unconnected-(U5-BP-Pad4)") (class "Default")
      (node (ref "U5") (pin "4") (pinfunction "BP_4") (pintype "input"))
    )
    (net (code "80") (name "unconnected-(U8-BOOTSEL-PadP$9)") (class "Default")
      (node (ref "U8") (pin "P$9") (pinfunction "BOOTSEL_P$9") (pintype "bidirectional"))
    )
    (net (code "81") (name "unconnected-(U8-GPIO0-PadP$18)") (class "Default")
      (node (ref "U8") (pin "P$18") (pinfunction "GPIO0_P$18") (pintype "bidirectional"))
    )
    (net (code "82") (name "unconnected-(U8-GPIO1-PadP$17)") (class "Default")
      (node (ref "U8") (pin "P$17") (pinfunction "GPIO1_P$17") (pintype "bidirectional"))
    )
    (net (code "83") (name "unconnected-(U8-GPIO7-PadP$12)") (class "Default")
      (node (ref "U8") (pin "P$12") (pinfunction "GPIO7_P$12") (pintype "bidirectional"))
    )
    (net (code "84") (name "unconnected-(U8-GPIO8-PadP$5)") (class "Default")
      (node (ref "U8") (pin "P$5") (pinfunction "GPIO8_P$5") (pintype "bidirectional"))
    )
    (net (code "85") (name "unconnected-(U8-NC-PadP$4)") (class "Default")
      (node (ref "U8") (pin "P$4") (pinfunction "NC_P$4") (pintype "bidirectional"))
    )
    (net (code "86") (name "unconnected-(U8-NC-PadP$16)") (class "Default")
      (node (ref "U8") (pin "P$16") (pinfunction "NC_P$16") (pintype "bidirectional"))
    )
    (net (code "87") (name "unconnected-(U8-NRESET-PadP$8)") (class "Default")
      (node (ref "U8") (pin "P$8") (pinfunction "NRESET_P$8") (pintype "bidirectional"))
    )
    (net (code "88") (name "unconnected-(U8-RX-PadP$14)") (class "Default")
      (node (ref "U8") (pin "P$14") (pinfunction "RX_P$14") (pintype "bidirectional"))
    )
    (net (code "89") (name "unconnected-(U8-SYS_ON-PadP$7)") (class "Default")
      (node (ref "U8") (pin "P$7") (pinfunction "SYS_ON_P$7") (pintype "bidirectional"))
    )
    (net (code "90") (name "unconnected-(U10-PAD-PadP$2)") (class "Default")
      (node (ref "U10") (pin "P$2") (pinfunction "PAD_P$2") (pintype "bidirectional"))
    )
    (net (code "91") (name "unconnected-(U11-GNDX-Pad18)") (class "Default")
      (node (ref "U11") (pin "18") (pinfunction "GNDX_18") (pintype "bidirectional"))
    )
    (net (code "92") (name "unconnected-(U11-GPIO0-Pad9)") (class "Default")
      (node (ref "U11") (pin "9") (pinfunction "GPIO0_9") (pintype "bidirectional"))
    )
    (net (code "93") (name "unconnected-(U11-GPIO3-Pad20)") (class "Default")
      (node (ref "U11") (pin "20") (pinfunction "GPIO3_20") (pintype "bidirectional"))
    )
    (net (code "94") (name "unconnected-(U11-NIRQ-Pad11)") (class "Default")
      (node (ref "U11") (pin "11") (pinfunction "NIRQ_11") (pintype "bidirectional"))
    )
    (net (code "95") (name "unconnected-(U11-TXRAMP-Pad7)") (class "Default")
      (node (ref "U11") (pin "7") (pinfunction "TXRAMP_7") (pintype "bidirectional"))
    )
    (net (code "96") (name "unconnected-(U12-GNDX-Pad18)") (class "Default")
      (node (ref "U12") (pin "18") (pinfunction "GNDX_18") (pintype "bidirectional"))
    )
    (net (code "97") (name "unconnected-(U12-GPIO0-Pad9)") (class "Default")
      (node (ref "U12") (pin "9") (pinfunction "GPIO0_9") (pintype "bidirectional"))
    )
    (net (code "98") (name "unconnected-(U12-GPIO2-Pad19)") (class "Default")
      (node (ref "U12") (pin "19") (pinfunction "GPIO2_19") (pintype "bidirectional"))
    )
    (net (code "99") (name "unconnected-(U12-NIRQ-Pad11)") (class "Default")
      (node (ref "U12") (pin "11") (pinfunction "NIRQ_11") (pintype "bidirectional"))
    )
    (net (code "100") (name "unconnected-(U12-TX-Pad4)") (class "Default")
      (node (ref "U12") (pin "4") (pinfunction "TX_4") (pintype "output"))
    )
    (net (code "101") (name "unconnected-(U12-TXRAMP-Pad7)") (class "Default")
      (node (ref "U12") (pin "7") (pinfunction "TXRAMP_7") (pintype "bidirectional"))
    )
    (net (code "102") (name "~{EEPROM_WRITE_EN}") (class "Default")
      (node (ref "R6") (pin "2") (pinfunction "2_2") (pintype "passive"))
      (node (ref "U13") (pin "3") (pinfunction "OSC_OUT/PC15_3") (pintype "bidirectional"))
      (node (ref "U6") (pin "5") (pinfunction "WP_5") (pintype "bidirectional"))
    )
  )
)
